# MB_pl_io_v1.net
KiCad netlist of a schematic drawn in Altium Designer
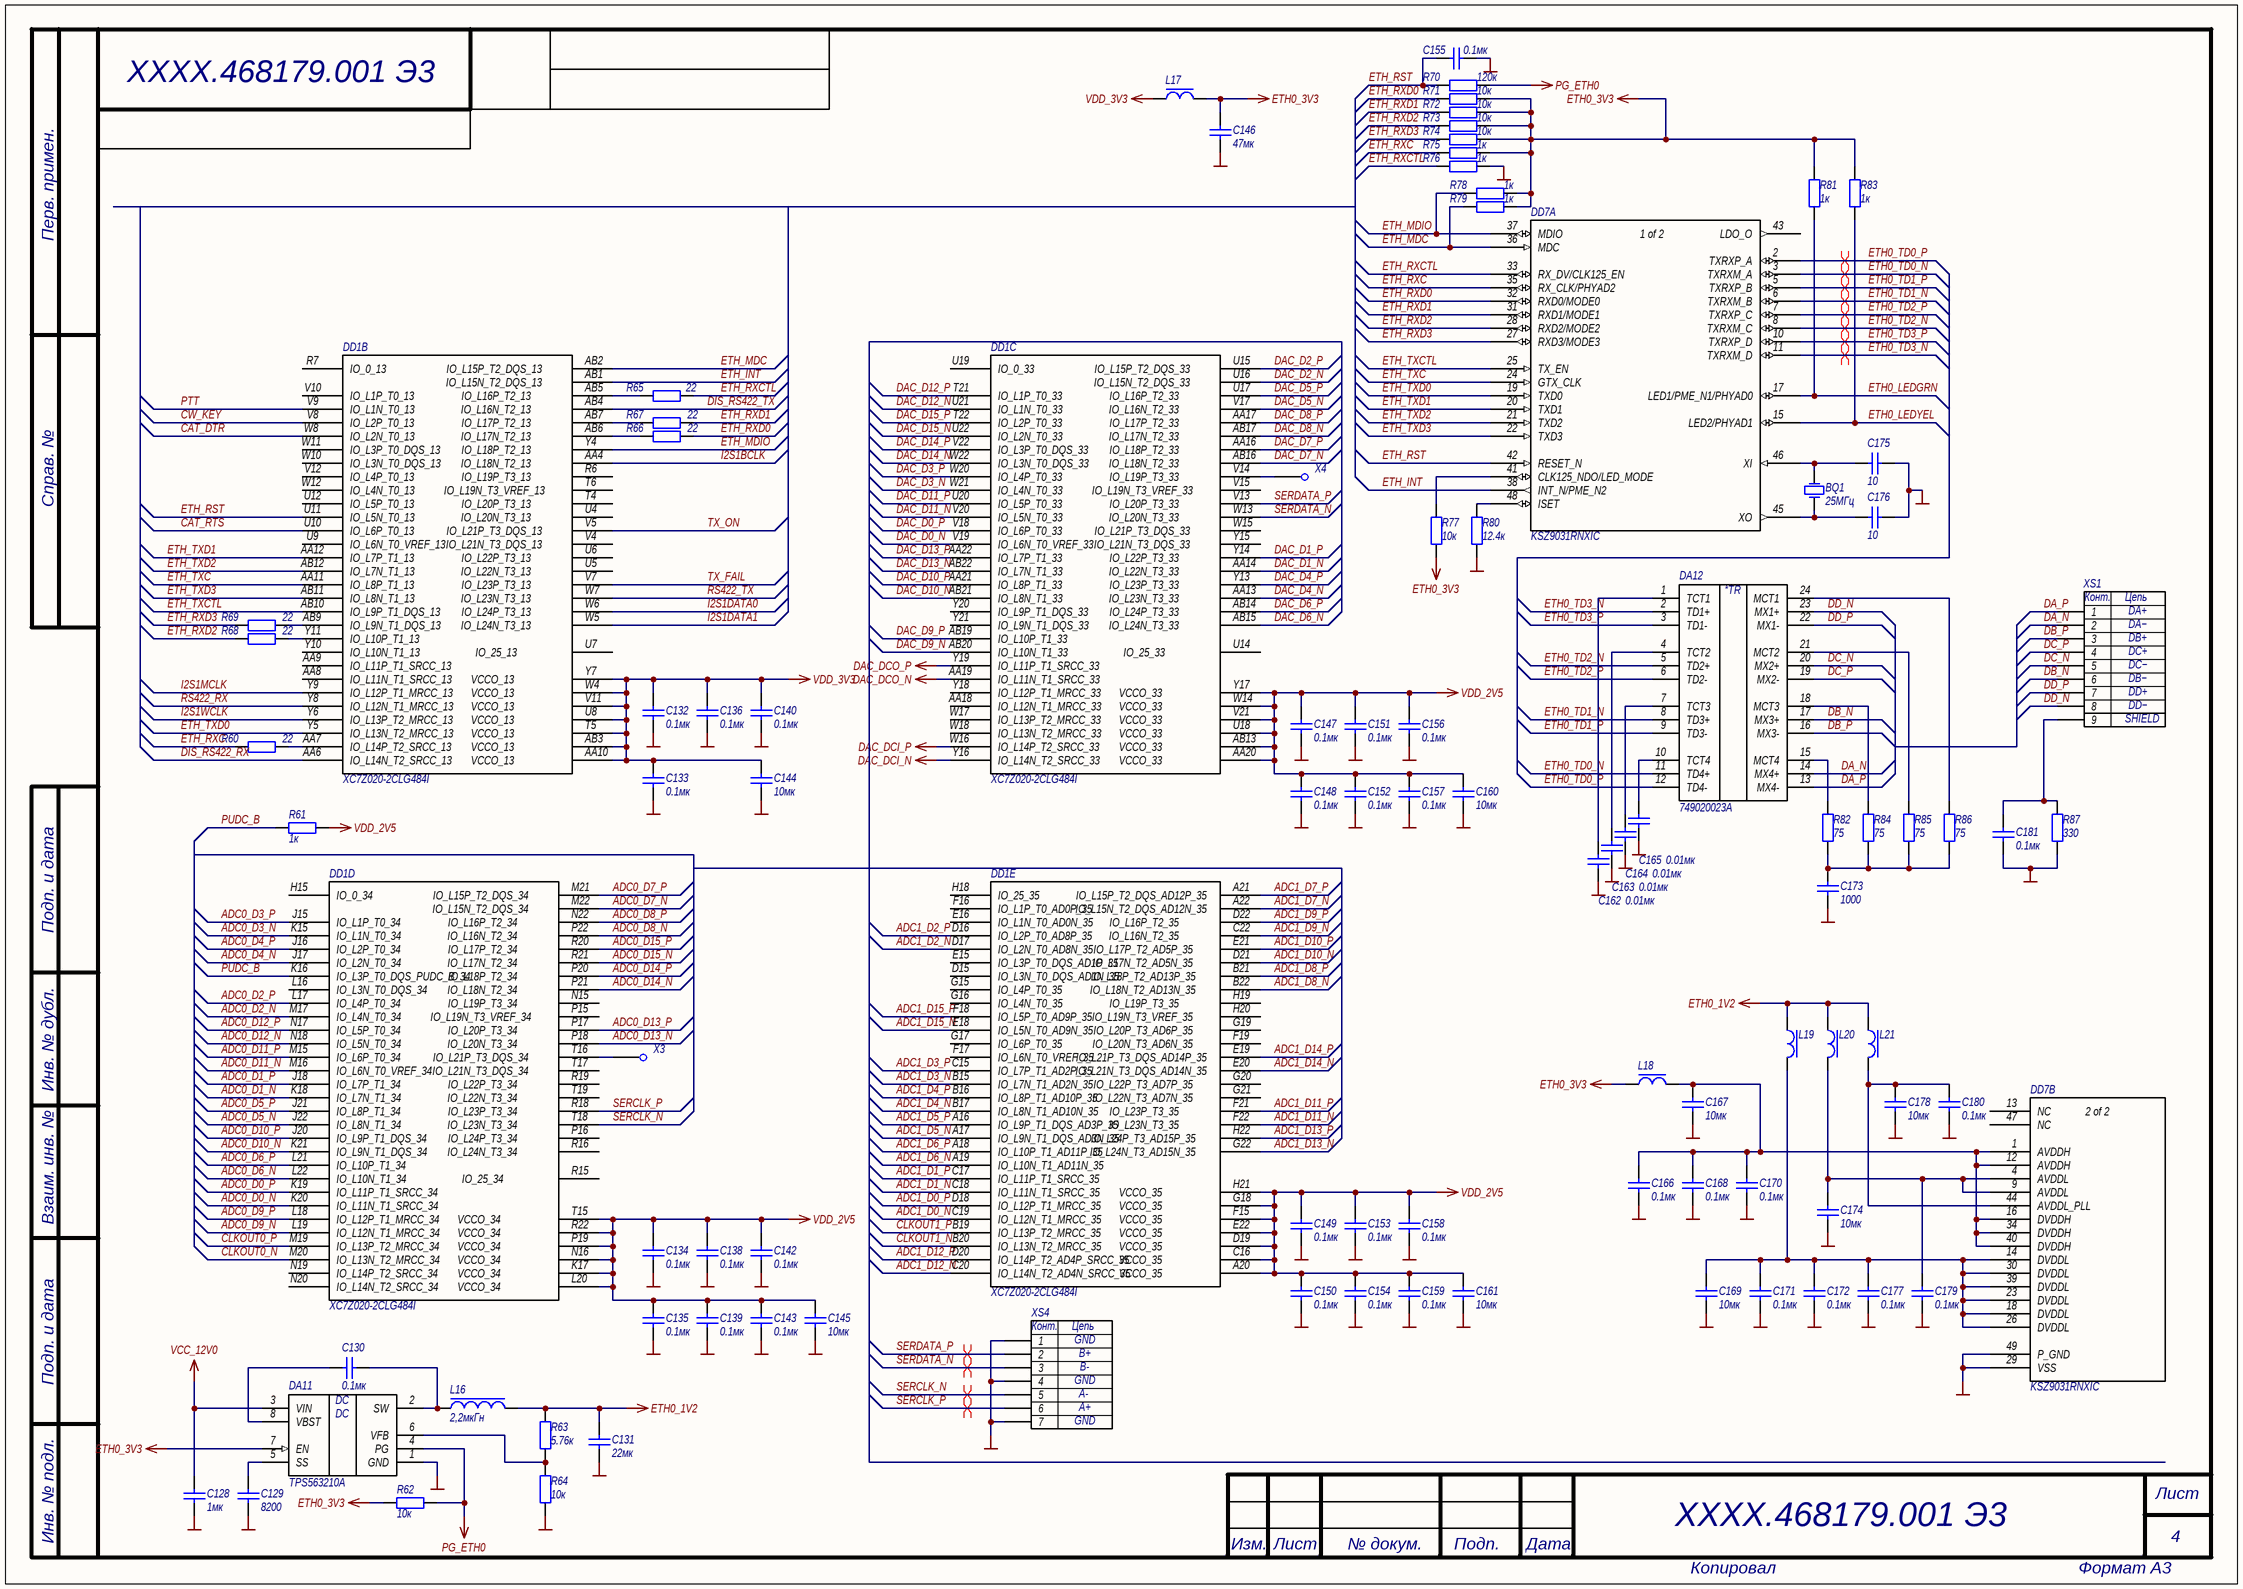
[diagram p0: MB_pl_io_v1.SchDoc]

(export (version "E")
  (design (tool "Eeschema 10.0.6"))
  (components
    (comp (ref "BQ1")
      (value "25МГц")
      (footprint "ABRACOM ABM10")
      (description "Резонатор кварцевый")
      (fields (field (name "TOLERANCE") "±20 ppm") (field (name "MANUFACTURER") "ABRACON"))
      (libsource (lib "nels_other") (part "Кварц ABM10-25.000MHZ-D30"))
    )
    (comp (ref "C128")
      (value "1мк")
      (footprint "CAPC1005X06N")
      (description "Кер. ЧИП-конденсатор")
      (fields (field (name "TOLERANCE") "±10%"))
      (libsource (lib "nels_caps") (part "Кер.ЧИП конд. 0402 1мкФ X5R 10%, 10В"))
    )
    (comp (ref "C129")
      (value "8200")
      (footprint "CAPC1005X06N")
      (description "Кер. ЧИП-конденсатор")
      (fields (field (name "TOLERANCE") "±20%"))
      (libsource (lib "nels_caps") (part "Кер.ЧИП конд. 0402 8200пФ X7R 10%, 50В"))
    )
    (comp (ref "C130")
      (value "0.1мк")
      (footprint "CAPC1005X06N")
      (description "Кер. ЧИП-конденсатор")
      (fields (field (name "TOLERANCE") "±10%"))
      (libsource (lib "nels") (part "Кер.ЧИП конд. 0402 0.1мкФ X7R 10%, 16В"))
    )
    (comp (ref "C131")
      (value "22мк")
      (footprint "CAPC2012X12L")
      (description "Кер. ЧИП-конденсатор")
      (fields (field (name "MANUFACTURER") "TDK") (field (name "TOLERANCE") "±10%"))
      (libsource (lib "nels_caps") (part "Кер.ЧИП конд. 0805 22мкФ X5R 10% 16В"))
    )
    (comp (ref "C132")
      (value "0.1мк")
      (footprint "CAPC1005X06N")
      (description "Кер. ЧИП-конденсатор")
      (fields (field (name "TOLERANCE") "±10%"))
      (libsource (lib "nels") (part "Кер.ЧИП конд. 0402 0.1мкФ X7R 10%, 16В"))
    )
    (comp (ref "C133")
      (value "0.1мк")
      (footprint "CAPC1005X06N")
      (description "Кер. ЧИП-конденсатор")
      (fields (field (name "TOLERANCE") "±10%"))
      (libsource (lib "nels") (part "Кер.ЧИП конд. 0402 0.1мкФ X7R 10%, 16В"))
    )
    (comp (ref "C134")
      (value "0.1мк")
      (footprint "CAPC1005X06N")
      (description "Кер. ЧИП-конденсатор")
      (fields (field (name "TOLERANCE") "±10%"))
      (libsource (lib "nels") (part "Кер.ЧИП конд. 0402 0.1мкФ X7R 10%, 16В"))
    )
    (comp (ref "C135")
      (value "0.1мк")
      (footprint "CAPC1005X06N")
      (description "Кер. ЧИП-конденсатор")
      (fields (field (name "TOLERANCE") "±10%"))
      (libsource (lib "nels") (part "Кер.ЧИП конд. 0402 0.1мкФ X7R 10%, 16В"))
    )
    (comp (ref "C136")
      (value "0.1мк")
      (footprint "CAPC1005X06N")
      (description "Кер. ЧИП-конденсатор")
      (fields (field (name "TOLERANCE") "±10%"))
      (libsource (lib "nels") (part "Кер.ЧИП конд. 0402 0.1мкФ X7R 10%, 16В"))
    )
    (comp (ref "C138")
      (value "0.1мк")
      (footprint "CAPC1005X06N")
      (description "Кер. ЧИП-конденсатор")
      (fields (field (name "TOLERANCE") "±10%"))
      (libsource (lib "nels") (part "Кер.ЧИП конд. 0402 0.1мкФ X7R 10%, 16В"))
    )
    (comp (ref "C139")
      (value "0.1мк")
      (footprint "CAPC1005X06N")
      (description "Кер. ЧИП-конденсатор")
      (fields (field (name "TOLERANCE") "±10%"))
      (libsource (lib "nels") (part "Кер.ЧИП конд. 0402 0.1мкФ X7R 10%, 16В"))
    )
    (comp (ref "C140")
      (value "0.1мк")
      (footprint "CAPC1005X06N")
      (description "Кер. ЧИП-конденсатор")
      (fields (field (name "TOLERANCE") "±10%"))
      (libsource (lib "nels") (part "Кер.ЧИП конд. 0402 0.1мкФ X7R 10%, 16В"))
    )
    (comp (ref "C142")
      (value "0.1мк")
      (footprint "CAPC1005X06N")
      (description "Кер. ЧИП-конденсатор")
      (fields (field (name "TOLERANCE") "±10%"))
      (libsource (lib "nels") (part "Кер.ЧИП конд. 0402 0.1мкФ X7R 10%, 16В"))
    )
    (comp (ref "C143")
      (value "0.1мк")
      (footprint "CAPC1005X06N")
      (description "Кер. ЧИП-конденсатор")
      (fields (field (name "TOLERANCE") "±10%"))
      (libsource (lib "nels") (part "Кер.ЧИП конд. 0402 0.1мкФ X7R 10%, 16В"))
    )
    (comp (ref "C144")
      (value "10мк")
      (footprint "CAPC1608X08L")
      (description "Кер. ЧИП-конденсатор")
      (fields (field (name "MANUFACTURER") "Murata") (field (name "TOLERANCE") "±20%"))
      (libsource (lib "nels_caps") (part "Кер.ЧИП конд. 0603 10мкФ X5R 20% 6.3В"))
    )
    (comp (ref "C145")
      (value "10мк")
      (footprint "CAPC1608X08L")
      (description "Кер. ЧИП-конденсатор")
      (fields (field (name "MANUFACTURER") "Murata") (field (name "TOLERANCE") "±20%"))
      (libsource (lib "nels_caps") (part "Кер.ЧИП конд. 0603 10мкФ X5R 20% 6.3В"))
    )
    (comp (ref "C146")
      (value "47мк")
      (footprint "CAPC2012X12L")
      (description "Кер. ЧИП-конденсатор")
      (fields (field (name "MANUFACTURER") "Murata") (field (name "TOLERANCE") "±20%"))
      (libsource (lib "nels_caps") (part "Кер.ЧИП конд. 0805 47мкФ X5R 20% 10В"))
    )
    (comp (ref "C147")
      (value "0.1мк")
      (footprint "CAPC1005X06N")
      (description "Кер. ЧИП-конденсатор")
      (fields (field (name "TOLERANCE") "±10%"))
      (libsource (lib "nels") (part "Кер.ЧИП конд. 0402 0.1мкФ X7R 10%, 16В"))
    )
    (comp (ref "C148")
      (value "0.1мк")
      (footprint "CAPC1005X06N")
      (description "Кер. ЧИП-конденсатор")
      (fields (field (name "TOLERANCE") "±10%"))
      (libsource (lib "nels") (part "Кер.ЧИП конд. 0402 0.1мкФ X7R 10%, 16В"))
    )
    (comp (ref "C149")
      (value "0.1мк")
      (footprint "CAPC1005X06N")
      (description "Кер. ЧИП-конденсатор")
      (fields (field (name "TOLERANCE") "±10%"))
      (libsource (lib "nels") (part "Кер.ЧИП конд. 0402 0.1мкФ X7R 10%, 16В"))
    )
    (comp (ref "C150")
      (value "0.1мк")
      (footprint "CAPC1005X06N")
      (description "Кер. ЧИП-конденсатор")
      (fields (field (name "TOLERANCE") "±10%"))
      (libsource (lib "nels") (part "Кер.ЧИП конд. 0402 0.1мкФ X7R 10%, 16В"))
    )
    (comp (ref "C151")
      (value "0.1мк")
      (footprint "CAPC1005X06N")
      (description "Кер. ЧИП-конденсатор")
      (fields (field (name "TOLERANCE") "±10%"))
      (libsource (lib "nels") (part "Кер.ЧИП конд. 0402 0.1мкФ X7R 10%, 16В"))
    )
    (comp (ref "C152")
      (value "0.1мк")
      (footprint "CAPC1005X06N")
      (description "Кер. ЧИП-конденсатор")
      (fields (field (name "TOLERANCE") "±10%"))
      (libsource (lib "nels") (part "Кер.ЧИП конд. 0402 0.1мкФ X7R 10%, 16В"))
    )
    (comp (ref "C153")
      (value "0.1мк")
      (footprint "CAPC1005X06N")
      (description "Кер. ЧИП-конденсатор")
      (fields (field (name "TOLERANCE") "±10%"))
      (libsource (lib "nels") (part "Кер.ЧИП конд. 0402 0.1мкФ X7R 10%, 16В"))
    )
    (comp (ref "C154")
      (value "0.1мк")
      (footprint "CAPC1005X06N")
      (description "Кер. ЧИП-конденсатор")
      (fields (field (name "TOLERANCE") "±10%"))
      (libsource (lib "nels") (part "Кер.ЧИП конд. 0402 0.1мкФ X7R 10%, 16В"))
    )
    (comp (ref "C155")
      (value "0.1мк")
      (footprint "CAPC1005X06N")
      (description "Кер. ЧИП-конденсатор")
      (fields (field (name "TOLERANCE") "±10%"))
      (libsource (lib "nels") (part "Кер.ЧИП конд. 0402 0.1мкФ X7R 10%, 16В"))
    )
    (comp (ref "C156")
      (value "0.1мк")
      (footprint "CAPC1005X06N")
      (description "Кер. ЧИП-конденсатор")
      (fields (field (name "TOLERANCE") "±10%"))
      (libsource (lib "nels") (part "Кер.ЧИП конд. 0402 0.1мкФ X7R 10%, 16В"))
    )
    (comp (ref "C157")
      (value "0.1мк")
      (footprint "CAPC1005X06N")
      (description "Кер. ЧИП-конденсатор")
      (fields (field (name "TOLERANCE") "±10%"))
      (libsource (lib "nels") (part "Кер.ЧИП конд. 0402 0.1мкФ X7R 10%, 16В"))
    )
    (comp (ref "C158")
      (value "0.1мк")
      (footprint "CAPC1005X06N")
      (description "Кер. ЧИП-конденсатор")
      (fields (field (name "TOLERANCE") "±10%"))
      (libsource (lib "nels") (part "Кер.ЧИП конд. 0402 0.1мкФ X7R 10%, 16В"))
    )
    (comp (ref "C159")
      (value "0.1мк")
      (footprint "CAPC1005X06N")
      (description "Кер. ЧИП-конденсатор")
      (fields (field (name "TOLERANCE") "±10%"))
      (libsource (lib "nels") (part "Кер.ЧИП конд. 0402 0.1мкФ X7R 10%, 16В"))
    )
    (comp (ref "C160")
      (value "10мк")
      (footprint "CAPC1608X08L")
      (description "Кер. ЧИП-конденсатор")
      (fields (field (name "MANUFACTURER") "Murata") (field (name "TOLERANCE") "±20%"))
      (libsource (lib "nels_caps") (part "Кер.ЧИП конд. 0603 10мкФ X5R 20% 6.3В"))
    )
    (comp (ref "C161")
      (value "10мк")
      (footprint "CAPC1608X08L")
      (description "Кер. ЧИП-конденсатор")
      (fields (field (name "MANUFACTURER") "Murata") (field (name "TOLERANCE") "±20%"))
      (libsource (lib "nels_caps") (part "Кер.ЧИП конд. 0603 10мкФ X5R 20% 6.3В"))
    )
    (comp (ref "C162")
      (value "0.01мк")
      (footprint "CAPC1005X06N")
      (description "Кер. ЧИП-конденсатор")
      (fields (field (name "TOLERANCE") "±20%"))
      (libsource (lib "nels_caps") (part "Кер.ЧИП конд. 0402 0.01мкФ X7R 10%, 50В"))
    )
    (comp (ref "C163")
      (value "0.01мк")
      (footprint "CAPC1005X06N")
      (description "Кер. ЧИП-конденсатор")
      (fields (field (name "TOLERANCE") "±20%"))
      (libsource (lib "nels_caps") (part "Кер.ЧИП конд. 0402 0.01мкФ X7R 10%, 50В"))
    )
    (comp (ref "C164")
      (value "0.01мк")
      (footprint "CAPC1005X06N")
      (description "Кер. ЧИП-конденсатор")
      (fields (field (name "TOLERANCE") "±20%"))
      (libsource (lib "nels_caps") (part "Кер.ЧИП конд. 0402 0.01мкФ X7R 10%, 50В"))
    )
    (comp (ref "C165")
      (value "0.01мк")
      (footprint "CAPC1005X06N")
      (description "Кер. ЧИП-конденсатор")
      (fields (field (name "TOLERANCE") "±20%"))
      (libsource (lib "nels_caps") (part "Кер.ЧИП конд. 0402 0.01мкФ X7R 10%, 50В"))
    )
    (comp (ref "C166")
      (value "0.1мк")
      (footprint "CAPC1005X06N")
      (description "Кер. ЧИП-конденсатор")
      (fields (field (name "TOLERANCE") "±10%"))
      (libsource (lib "nels_caps") (part "Кер.ЧИП конд. 0402 0.1мкФ X7R 10%, 16В"))
    )
    (comp (ref "C167")
      (value "10мк")
      (footprint "CAPC1608X08L")
      (description "Кер. ЧИП-конденсатор")
      (fields (field (name "MANUFACTURER") "Murata") (field (name "TOLERANCE") "±20%"))
      (libsource (lib "nels_caps") (part "Кер.ЧИП конд. 0603 10мкФ X5R 20% 6.3В"))
    )
    (comp (ref "C168")
      (value "0.1мк")
      (footprint "CAPC1005X06N")
      (description "Кер. ЧИП-конденсатор")
      (fields (field (name "TOLERANCE") "±10%"))
      (libsource (lib "nels_caps") (part "Кер.ЧИП конд. 0402 0.1мкФ X7R 10%, 16В"))
    )
    (comp (ref "C169")
      (value "10мк")
      (footprint "CAPC1608X08L")
      (description "Кер. ЧИП-конденсатор")
      (fields (field (name "MANUFACTURER") "Murata") (field (name "TOLERANCE") "±20%"))
      (libsource (lib "nels_caps") (part "Кер.ЧИП конд. 0603 10мкФ X5R 20% 6.3В"))
    )
    (comp (ref "C170")
      (value "0.1мк")
      (footprint "CAPC1005X06N")
      (description "Кер. ЧИП-конденсатор")
      (fields (field (name "TOLERANCE") "±10%"))
      (libsource (lib "nels_caps") (part "Кер.ЧИП конд. 0402 0.1мкФ X7R 10%, 16В"))
    )
    (comp (ref "C171")
      (value "0.1мк")
      (footprint "CAPC1005X06N")
      (description "Кер. ЧИП-конденсатор")
      (fields (field (name "TOLERANCE") "±10%"))
      (libsource (lib "nels_caps") (part "Кер.ЧИП конд. 0402 0.1мкФ X7R 10%, 16В"))
    )
    (comp (ref "C172")
      (value "0.1мк")
      (footprint "CAPC1005X06N")
      (description "Кер. ЧИП-конденсатор")
      (fields (field (name "TOLERANCE") "±10%"))
      (libsource (lib "nels_caps") (part "Кер.ЧИП конд. 0402 0.1мкФ X7R 10%, 16В"))
    )
    (comp (ref "C173")
      (value "1000")
      (footprint "CAPC1005X06N")
      (description "Кер. ЧИП-конденсатор")
      (fields (field (name "TOLERANCE") "±5%"))
      (libsource (lib "nels_caps") (part "Кер.ЧИП конд. 0402 1000пФ NP0 5%, 50В"))
    )
    (comp (ref "C174")
      (value "10мк")
      (footprint "CAPC1608X08L")
      (description "Кер. ЧИП-конденсатор")
      (fields (field (name "MANUFACTURER") "Murata") (field (name "TOLERANCE") "±20%"))
      (libsource (lib "nels_caps") (part "Кер.ЧИП конд. 0603 10мкФ X5R 20% 6.3В"))
    )
    (comp (ref "C175")
      (value "10")
      (footprint "CAPC1005X06N")
      (description "Кер. ЧИП-конденсатор")
      (fields (field (name "TOLERANCE") "±5%"))
      (libsource (lib "nels_caps") (part "Кер.ЧИП конд. 0402 10пФ NPO 5%, 50В"))
    )
    (comp (ref "C176")
      (value "10")
      (footprint "CAPC1005X06N")
      (description "Кер. ЧИП-конденсатор")
      (fields (field (name "TOLERANCE") "±5%"))
      (libsource (lib "nels_caps") (part "Кер.ЧИП конд. 0402 10пФ NPO 5%, 50В"))
    )
    (comp (ref "C177")
      (value "0.1мк")
      (footprint "CAPC1005X06N")
      (description "Кер. ЧИП-конденсатор")
      (fields (field (name "TOLERANCE") "±10%"))
      (libsource (lib "nels_caps") (part "Кер.ЧИП конд. 0402 0.1мкФ X7R 10%, 16В"))
    )
    (comp (ref "C178")
      (value "10мк")
      (footprint "CAPC1608X08L")
      (description "Кер. ЧИП-конденсатор")
      (fields (field (name "MANUFACTURER") "Murata") (field (name "TOLERANCE") "±20%"))
      (libsource (lib "nels_caps") (part "Кер.ЧИП конд. 0603 10мкФ X5R 20% 6.3В"))
    )
    (comp (ref "C179")
      (value "0.1мк")
      (footprint "CAPC1005X06N")
      (description "Кер. ЧИП-конденсатор")
      (fields (field (name "TOLERANCE") "±10%"))
      (libsource (lib "nels_caps") (part "Кер.ЧИП конд. 0402 0.1мкФ X7R 10%, 16В"))
    )
    (comp (ref "C180")
      (value "0.1мк")
      (footprint "CAPC1005X06N")
      (description "Кер. ЧИП-конденсатор")
      (fields (field (name "TOLERANCE") "±10%"))
      (libsource (lib "nels_caps") (part "Кер.ЧИП конд. 0402 0.1мкФ X7R 10%, 16В"))
    )
    (comp (ref "C181")
      (value "0.1мк")
      (footprint "CAPC1608X08L")
      (description "Кер. ЧИП-конденсатор")
      (fields (field (name "TOLERANCE") "±10%") (field (name "MANUFACTURER") "Murata"))
      (libsource (lib "nels_caps") (part "Кер.ЧИП конд. 0603 0.1мкФ X7R 10% 50В"))
    )
    (comp (ref "DA11")
      (value "TPS563210A")
      (footprint "TSOP65P280X110-8N")
      (description "TPS56x210A, 4.5-V to 17-V Input, 2-A, 3-A Synchrono")
      (fields (field (name "MANUFACTURER") "TI"))
      (libsource (lib "MB") (part "Микросхема TPS563210A"))
    )
    (comp (ref "DA12")
      (value "749020023A")
      (footprint "749020023A")
      (description "1000BASE-T Magnetics Module")
      (fields (field (name "MANUFACTURER") "Wurth Elektronik"))
      (libsource (lib "nels_other") (part "Сборка трансформаторов 749020023A"))
    )
    (comp (ref "DD1")
      (value "XC7Z020-2CLG484I")
      (footprint "BGA484C80P22X22_1900X1900X160")
      (description "Zynq®-7000 SoC Family")
      (fields (field (name "MANUFACTURER") "XILINX"))
      (libsource (lib "MB") (part "Микросхема XC7Z020-2CLG484I"))
    )
    (comp (ref "DD7")
      (value "KSZ9031RNXIC")
      (footprint "QFN50P700X700-48V6M")
      (description "Gigabit Ethernet Transceiver with Power Saving Features")
      (fields (field (name "COPYRIGHT") "Copyright (C) 2018 Accelerated Designs. All rights reserved"))
      (libsource (lib "nels_chip") (part "Микросхема KSZ9031RNXIC"))
    )
    (comp (ref "L16")
      (value "2,2мкГн")
      (footprint "CSAB0420")
      (description "Molding Power Choke")
      (fields
        (field (name "MANUFACTURER") "Vishay")
        (field (name "MANUFACTURERPARTNUMBER") "IHLP1616ABER1R0M11")
      )
      (libsource (lib "nels_ind") (part "ЧИП индуктивность CSAB0420-2R2M"))
    )
    (comp (ref "L17")
      (value "BLM18PG121SN1D")
      (footprint "INDC1608X08L")
      (description "SMD EMI Suppression Filter EMIFIL")
      (fields (field (name "MANUFACTURER") "Murata"))
      (libsource (lib "nels_ind") (part "ЧИП дроссель 0603 BLM18PG121SN1D"))
    )
    (comp (ref "L18")
      (value "BLM18PG121SN1D")
      (footprint "INDC1608X08L")
      (description "SMD EMI Suppression Filter EMIFIL")
      (fields (field (name "MANUFACTURER") "Murata"))
      (libsource (lib "nels_ind") (part "ЧИП дроссель 0603 BLM18PG121SN1D"))
    )
    (comp (ref "L19")
      (value "BLM18PG121SN1D")
      (footprint "INDC1608X08L")
      (description "SMD EMI Suppression Filter EMIFIL")
      (fields (field (name "MANUFACTURER") "Murata"))
      (libsource (lib "nels_ind") (part "ЧИП дроссель 0603 BLM18PG121SN1D"))
    )
    (comp (ref "L20")
      (value "BLM18PG121SN1D")
      (footprint "INDC1608X08L")
      (description "SMD EMI Suppression Filter EMIFIL")
      (fields (field (name "MANUFACTURER") "Murata"))
      (libsource (lib "nels_ind") (part "ЧИП дроссель 0603 BLM18PG121SN1D"))
    )
    (comp (ref "L21")
      (value "BLM18PG121SN1D")
      (footprint "INDC1608X08L")
      (description "SMD EMI Suppression Filter EMIFIL")
      (fields (field (name "MANUFACTURER") "Murata"))
      (libsource (lib "nels_ind") (part "ЧИП дроссель 0603 BLM18PG121SN1D"))
    )
    (comp (ref "R60")
      (value "22")
      (footprint "RESC1005X06N")
      (description "ЧИП-резистор")
      (fields (field (name "TOLERANCE") "±5%"))
      (libsource (lib "nels_res") (part "Чип резистор 0402 22 Ом, 5%"))
    )
    (comp (ref "R61")
      (value "1к")
      (footprint "RESC1005X06N")
      (description "ЧИП-резистор")
      (fields (field (name "TOLERANCE") "±5%"))
      (libsource (lib "nels_res") (part "Чип резистор 0402 1 кОм, 5%"))
    )
    (comp (ref "R62")
      (value "10к")
      (footprint "RESC1005X06N")
      (description "ЧИП-резистор")
      (fields (field (name "TOLERANCE") "±5%"))
      (libsource (lib "nels_res") (part "Чип резистор 0402 10 кОм, 1%"))
    )
    (comp (ref "R63")
      (value "5.76к")
      (footprint "RESC1005X06N")
      (description "ЧИП-резистор")
      (fields (field (name "TOLERANCE") "±1%"))
      (libsource (lib "nels_res") (part "Чип резистор 0402 5,76 кОм, 1%"))
    )
    (comp (ref "R64")
      (value "10к")
      (footprint "RESC1005X06N")
      (description "ЧИП-резистор")
      (fields (field (name "TOLERANCE") "±5%"))
      (libsource (lib "") (part "Чип резистор 0402 10 кОм, 5%_1"))
    )
    (comp (ref "R65")
      (value "22")
      (footprint "RESC1005X06N")
      (description "ЧИП-резистор")
      (fields (field (name "TOLERANCE") "±5%"))
      (libsource (lib "") (part "Чип резистор 0402 22 Ом, 5%_1"))
    )
    (comp (ref "R66")
      (value "22")
      (footprint "RESC1005X06N")
      (description "ЧИП-резистор")
      (fields (field (name "TOLERANCE") "±5%"))
      (libsource (lib "nels_res") (part "Чип резистор 0402 22 Ом, 5%"))
    )
    (comp (ref "R67")
      (value "22")
      (footprint "RESC1005X06N")
      (description "ЧИП-резистор")
      (fields (field (name "TOLERANCE") "±5%"))
      (libsource (lib "nels_res") (part "Чип резистор 0402 22 Ом, 5%"))
    )
    (comp (ref "R68")
      (value "22")
      (footprint "RESC1005X06N")
      (description "ЧИП-резистор")
      (fields (field (name "TOLERANCE") "±5%"))
      (libsource (lib "nels_res") (part "Чип резистор 0402 22 Ом, 5%"))
    )
    (comp (ref "R69")
      (value "22")
      (footprint "RESC1005X06N")
      (description "ЧИП-резистор")
      (fields (field (name "TOLERANCE") "±5%"))
      (libsource (lib "nels_res") (part "Чип резистор 0402 22 Ом, 5%"))
    )
    (comp (ref "R70")
      (value "120к")
      (footprint "RESC1005X06N")
      (description "ЧИП-резистор")
      (fields (field (name "TOLERANCE") "±5%"))
      (libsource (lib "nels_res") (part "Чип резистор 0402 120 кОм, 5%"))
    )
    (comp (ref "R71")
      (value "10к")
      (footprint "RESC1005X06N")
      (description "ЧИП-резистор")
      (fields (field (name "TOLERANCE") "±5%"))
      (libsource (lib "nels_res") (part "Чип резистор 0402 10 кОм, 5%"))
    )
    (comp (ref "R72")
      (value "10к")
      (footprint "RESC1005X06N")
      (description "ЧИП-резистор")
      (fields (field (name "TOLERANCE") "±5%"))
      (libsource (lib "nels_res") (part "Чип резистор 0402 10 кОм, 5%"))
    )
    (comp (ref "R73")
      (value "10к")
      (footprint "RESC1005X06N")
      (description "ЧИП-резистор")
      (fields (field (name "TOLERANCE") "±5%"))
      (libsource (lib "nels_res") (part "Чип резистор 0402 10 кОм, 5%"))
    )
    (comp (ref "R74")
      (value "10к")
      (footprint "RESC1005X06N")
      (description "ЧИП-резистор")
      (fields (field (name "TOLERANCE") "±5%"))
      (libsource (lib "nels_res") (part "Чип резистор 0402 10 кОм, 5%"))
    )
    (comp (ref "R75")
      (value "1к")
      (footprint "RESC1005X06N")
      (description "ЧИП-резистор")
      (fields (field (name "TOLERANCE") "±5%"))
      (libsource (lib "nels_res") (part "Чип резистор 0402 1 кОм, 5%"))
    )
    (comp (ref "R76")
      (value "1к")
      (footprint "RESC1005X06N")
      (description "ЧИП-резистор")
      (fields (field (name "TOLERANCE") "±5%"))
      (libsource (lib "nels_res") (part "Чип резистор 0402 1 кОм, 5%"))
    )
    (comp (ref "R77")
      (value "10к")
      (footprint "RESC1005X06N")
      (description "ЧИП-резистор")
      (fields (field (name "TOLERANCE") "±5%"))
      (libsource (lib "") (part "Чип резистор 0402 10 кОм, 5%_1"))
    )
    (comp (ref "R78")
      (value "1к")
      (footprint "RESC1005X06N")
      (description "ЧИП-резистор")
      (fields (field (name "TOLERANCE") "±5%"))
      (libsource (lib "nels_res") (part "Чип резистор 0402 1 кОм, 5%"))
    )
    (comp (ref "R79")
      (value "1к")
      (footprint "RESC1005X06N")
      (description "ЧИП-резистор")
      (fields (field (name "TOLERANCE") "±5%"))
      (libsource (lib "nels_res") (part "Чип резистор 0402 1 кОм, 5%"))
    )
    (comp (ref "R80")
      (value "12.4к")
      (footprint "RESC1005X06N")
      (description "ЧИП-резистор")
      (fields (field (name "TOLERANCE") "±1%"))
      (libsource (lib "nels_res") (part "Чип резистор 0402 12.4 кОм, 1%"))
    )
    (comp (ref "R81")
      (value "1к")
      (footprint "RESC1005X06N")
      (description "ЧИП-резистор")
      (fields (field (name "TOLERANCE") "±5%"))
      (libsource (lib "") (part "Чип резистор 0402 1 кОм, 5%_1"))
    )
    (comp (ref "R82")
      (value "75")
      (footprint "RESC1005X06N")
      (description "ЧИП-резистор")
      (fields (field (name "TOLERANCE") "±5%"))
      (libsource (lib "nels_res") (part "Чип резистор 0402 75 Ом, 5%"))
    )
    (comp (ref "R83")
      (value "1к")
      (footprint "RESC1005X06N")
      (description "ЧИП-резистор")
      (fields (field (name "TOLERANCE") "±5%"))
      (libsource (lib "") (part "Чип резистор 0402 1 кОм, 5%_1"))
    )
    (comp (ref "R84")
      (value "75")
      (footprint "RESC1005X06N")
      (description "ЧИП-резистор")
      (fields (field (name "TOLERANCE") "±5%"))
      (libsource (lib "nels_res") (part "Чип резистор 0402 75 Ом, 5%"))
    )
    (comp (ref "R85")
      (value "75")
      (footprint "RESC1005X06N")
      (description "ЧИП-резистор")
      (fields (field (name "TOLERANCE") "±5%"))
      (libsource (lib "nels_res") (part "Чип резистор 0402 75 Ом, 5%"))
    )
    (comp (ref "R86")
      (value "75")
      (footprint "RESC1005X06N")
      (description "ЧИП-резистор")
      (fields (field (name "TOLERANCE") "±5%"))
      (libsource (lib "nels_res") (part "Чип резистор 0402 75 Ом, 5%"))
    )
    (comp (ref "R87")
      (value "330")
      (footprint "RESC1005X06N")
      (description "ЧИП-резистор")
      (fields (field (name "TOLERANCE") "±5%"))
      (libsource (lib "nels_res") (part "Чип резистор 0402 330 Ом, 5%"))
    )
    (comp (ref "X3")
      (value "Конструктивный элемент")
      (footprint "PIN2_PROBE")
      (description "Соединитель")
      (libsource (lib "nels_conn") (part "Соединение под пайку"))
    )
    (comp (ref "X4")
      (value "Конструктивный элемент")
      (footprint "PIN2_PROBE")
      (description "Соединитель")
      (libsource (lib "nels_conn") (part "Соединение под пайку"))
    )
    (comp (ref "XS1")
      (value "TJ16S-8P8C")
      (footprint "KLS12-107L")
      (description "Modular Jack RJ45")
      (fields (field (name "MANUFACTURER") "KLS"))
      (libsource (lib "nels_conn") (part "Соединитель KLS12-107L-2-8P8C-0"))
    )
    (comp (ref "XS4")
      (value "KLS1-SATA001")
      (footprint "KLS1-SATA001")
      (description "SATA Type A 7P Male Connector,SMD")
      (fields (field (name "MANUFACTURER") "KLS"))
      (libsource (lib "nels_conn") (part "Соединитель KLS1-SATA001"))
    )
  )
  (nets
    (net (code "1") (name "/ADC0_D0_N") (class "Default")
      (node (ref "DD1") (pin "K20") (pinfunction "IO_L11N_T1_SRCC_34_K20") (pintype "passive"))
    )
    (net (code "2") (name "/ADC0_D0_P") (class "Default")
      (node (ref "DD1") (pin "K19") (pinfunction "IO_L11P_T1_SRCC_34_K19") (pintype "passive"))
    )
    (net (code "3") (name "/ADC0_D1_N") (class "Default")
      (node (ref "DD1") (pin "K18") (pinfunction "IO_L7N_T1_34_K18") (pintype "passive"))
    )
    (net (code "4") (name "/ADC0_D1_P") (class "Default")
      (node (ref "DD1") (pin "J18") (pinfunction "IO_L7P_T1_34_J18") (pintype "passive"))
    )
    (net (code "5") (name "/ADC0_D2_N") (class "Default")
      (node (ref "DD1") (pin "M17") (pinfunction "IO_L4N_T0_34_M17") (pintype "passive"))
    )
    (net (code "6") (name "/ADC0_D2_P") (class "Default")
      (node (ref "DD1") (pin "L17") (pinfunction "IO_L4P_T0_34_L17") (pintype "passive"))
    )
    (net (code "7") (name "/ADC0_D3_N") (class "Default")
      (node (ref "DD1") (pin "K15") (pinfunction "IO_L1N_T0_34_K15") (pintype "passive"))
    )
    (net (code "8") (name "/ADC0_D3_P") (class "Default")
      (node (ref "DD1") (pin "J15") (pinfunction "IO_L1P_T0_34_J15") (pintype "passive"))
    )
    (net (code "9") (name "/ADC0_D4_N") (class "Default")
      (node (ref "DD1") (pin "J17") (pinfunction "IO_L2N_T0_34_J17") (pintype "passive"))
    )
    (net (code "10") (name "/ADC0_D4_P") (class "Default")
      (node (ref "DD1") (pin "J16") (pinfunction "IO_L2P_T0_34_J16") (pintype "passive"))
    )
    (net (code "11") (name "/ADC0_D5_N") (class "Default")
      (node (ref "DD1") (pin "J22") (pinfunction "IO_L8N_T1_34_J22") (pintype "passive"))
    )
    (net (code "12") (name "/ADC0_D5_P") (class "Default")
      (node (ref "DD1") (pin "J21") (pinfunction "IO_L8P_T1_34_J21") (pintype "passive"))
    )
    (net (code "13") (name "/ADC0_D6_N") (class "Default")
      (node (ref "DD1") (pin "L22") (pinfunction "IO_L10N_T1_34_L22") (pintype "passive"))
    )
    (net (code "14") (name "/ADC0_D6_P") (class "Default")
      (node (ref "DD1") (pin "L21") (pinfunction "IO_L10P_T1_34_L21") (pintype "passive"))
    )
    (net (code "15") (name "/ADC0_D7_N") (class "Default")
      (node (ref "DD1") (pin "M22") (pinfunction "IO_L15N_T2_DQS_34_M22") (pintype "passive"))
    )
    (net (code "16") (name "/ADC0_D7_P") (class "Default")
      (node (ref "DD1") (pin "M21") (pinfunction "IO_L15P_T2_DQS_34_M21") (pintype "passive"))
    )
    (net (code "17") (name "/ADC0_D8_N") (class "Default")
      (node (ref "DD1") (pin "P22") (pinfunction "IO_L16N_T2_34_P22") (pintype "passive"))
    )
    (net (code "18") (name "/ADC0_D8_P") (class "Default")
      (node (ref "DD1") (pin "N22") (pinfunction "IO_L16P_T2_34_N22") (pintype "passive"))
    )
    (net (code "19") (name "/ADC0_D9_N") (class "Default")
      (node (ref "DD1") (pin "L19") (pinfunction "IO_L12N_T1_MRCC_34_L19") (pintype "passive"))
    )
    (net (code "20") (name "/ADC0_D9_P") (class "Default")
      (node (ref "DD1") (pin "L18") (pinfunction "IO_L12P_T1_MRCC_34_L18") (pintype "passive"))
    )
    (net (code "21") (name "/ADC0_D10_N") (class "Default")
      (node (ref "DD1") (pin "K21") (pinfunction "IO_L9N_T1_DQS_34_K21") (pintype "passive"))
    )
    (net (code "22") (name "/ADC0_D10_P") (class "Default")
      (node (ref "DD1") (pin "J20") (pinfunction "IO_L9P_T1_DQS_34_J20") (pintype "passive"))
    )
    (net (code "23") (name "/ADC0_D11_N") (class "Default")
      (node (ref "DD1") (pin "M16") (pinfunction "IO_L6N_T0_VREF_34_M16") (pintype "passive"))
    )
    (net (code "24") (name "/ADC0_D11_P") (class "Default")
      (node (ref "DD1") (pin "M15") (pinfunction "IO_L6P_T0_34_M15") (pintype "passive"))
    )
    (net (code "25") (name "/ADC0_D12_N") (class "Default")
      (node (ref "DD1") (pin "N18") (pinfunction "IO_L5N_T0_34_N18") (pintype "passive"))
    )
    (net (code "26") (name "/ADC0_D12_P") (class "Default")
      (node (ref "DD1") (pin "N17") (pinfunction "IO_L5P_T0_34_N17") (pintype "passive"))
    )
    (net (code "27") (name "/ADC0_D13_N") (class "Default")
      (node (ref "DD1") (pin "P18") (pinfunction "IO_L20N_T3_34_P18") (pintype "passive"))
    )
    (net (code "28") (name "/ADC0_D13_P") (class "Default")
      (node (ref "DD1") (pin "P17") (pinfunction "IO_L20P_T3_34_P17") (pintype "passive"))
    )
    (net (code "29") (name "/ADC0_D14_N") (class "Default")
      (node (ref "DD1") (pin "P21") (pinfunction "IO_L18N_T2_34_P21") (pintype "passive"))
    )
    (net (code "30") (name "/ADC0_D14_P") (class "Default")
      (node (ref "DD1") (pin "P20") (pinfunction "IO_L18P_T2_34_P20") (pintype "passive"))
    )
    (net (code "31") (name "/ADC0_D15_N") (class "Default")
      (node (ref "DD1") (pin "R21") (pinfunction "IO_L17N_T2_34_R21") (pintype "passive"))
    )
    (net (code "32") (name "/ADC0_D15_P") (class "Default")
      (node (ref "DD1") (pin "R20") (pinfunction "IO_L17P_T2_34_R20") (pintype "passive"))
    )
    (net (code "33") (name "/ADC1_D0_N") (class "Default")
      (node (ref "DD1") (pin "C19") (pinfunction "IO_L12N_T1_MRCC_35_C19") (pintype "passive"))
    )
    (net (code "34") (name "/ADC1_D0_P") (class "Default")
      (node (ref "DD1") (pin "D18") (pinfunction "IO_L12P_T1_MRCC_35_D18") (pintype "passive"))
    )
    (net (code "35") (name "/ADC1_D1_N") (class "Default")
      (node (ref "DD1") (pin "C18") (pinfunction "IO_L11N_T1_SRCC_35_C18") (pintype "passive"))
    )
    (net (code "36") (name "/ADC1_D1_P") (class "Default")
      (node (ref "DD1") (pin "C17") (pinfunction "IO_L11P_T1_SRCC_35_C17") (pintype "passive"))
    )
    (net (code "37") (name "/ADC1_D2_N") (class "Default")
      (node (ref "DD1") (pin "D17") (pinfunction "IO_L2N_T0_AD8N_35_D17") (pintype "passive"))
    )
    (net (code "38") (name "/ADC1_D2_P") (class "Default")
      (node (ref "DD1") (pin "D16") (pinfunction "IO_L2P_T0_AD8P_35_D16") (pintype "passive"))
    )
    (net (code "39") (name "/ADC1_D3_N") (class "Default")
      (node (ref "DD1") (pin "B15") (pinfunction "IO_L7N_T1_AD2N_35_B15") (pintype "passive"))
    )
    (net (code "40") (name "/ADC1_D3_P") (class "Default")
      (node (ref "DD1") (pin "C15") (pinfunction "IO_L7P_T1_AD2P_35_C15") (pintype "passive"))
    )
    (net (code "41") (name "/ADC1_D4_N") (class "Default")
      (node (ref "DD1") (pin "B17") (pinfunction "IO_L8N_T1_AD10N_35_B17") (pintype "passive"))
    )
    (net (code "42") (name "/ADC1_D4_P") (class "Default")
      (node (ref "DD1") (pin "B16") (pinfunction "IO_L8P_T1_AD10P_35_B16") (pintype "passive"))
    )
    (net (code "43") (name "/ADC1_D5_N") (class "Default")
      (node (ref "DD1") (pin "A17") (pinfunction "IO_L9N_T1_DQS_AD3N_35_A17") (pintype "passive"))
    )
    (net (code "44") (name "/ADC1_D5_P") (class "Default")
      (node (ref "DD1") (pin "A16") (pinfunction "IO_L9P_T1_DQS_AD3P_35_A16") (pintype "passive"))
    )
    (net (code "45") (name "/ADC1_D6_N") (class "Default")
      (node (ref "DD1") (pin "A19") (pinfunction "IO_L10N_T1_AD11N_35_A19") (pintype "passive"))
    )
    (net (code "46") (name "/ADC1_D6_P") (class "Default")
      (node (ref "DD1") (pin "A18") (pinfunction "IO_L10P_T1_AD11P_35_A18") (pintype "passive"))
    )
    (net (code "47") (name "/ADC1_D7_N") (class "Default")
      (node (ref "DD1") (pin "A22") (pinfunction "IO_L15N_T2_DQS_AD12N_35_A22") (pintype "passive"))
    )
    (net (code "48") (name "/ADC1_D7_P") (class "Default")
      (node (ref "DD1") (pin "A21") (pinfunction "IO_L15P_T2_DQS_AD12P_35_A21") (pintype "passive"))
    )
    (net (code "49") (name "/ADC1_D8_N") (class "Default")
      (node (ref "DD1") (pin "B22") (pinfunction "IO_L18N_T2_AD13N_35_B22") (pintype "passive"))
    )
    (net (code "50") (name "/ADC1_D8_P") (class "Default")
      (node (ref "DD1") (pin "B21") (pinfunction "IO_L18P_T2_AD13P_35_B21") (pintype "passive"))
    )
    (net (code "51") (name "/ADC1_D9_N") (class "Default")
      (node (ref "DD1") (pin "C22") (pinfunction "IO_L16N_T2_35_C22") (pintype "passive"))
    )
    (net (code "52") (name "/ADC1_D9_P") (class "Default")
      (node (ref "DD1") (pin "D22") (pinfunction "IO_L16P_T2_35_D22") (pintype "passive"))
    )
    (net (code "53") (name "/ADC1_D10_N") (class "Default")
      (node (ref "DD1") (pin "D21") (pinfunction "IO_L17N_T2_AD5N_35_D21") (pintype "passive"))
    )
    (net (code "54") (name "/ADC1_D10_P") (class "Default")
      (node (ref "DD1") (pin "E21") (pinfunction "IO_L17P_T2_AD5P_35_E21") (pintype "passive"))
    )
    (net (code "55") (name "/ADC1_D11_N") (class "Default")
      (node (ref "DD1") (pin "F22") (pinfunction "IO_L23N_T3_35_F22") (pintype "passive"))
    )
    (net (code "56") (name "/ADC1_D11_P") (class "Default")
      (node (ref "DD1") (pin "F21") (pinfunction "IO_L23P_T3_35_F21") (pintype "passive"))
    )
    (net (code "57") (name "/ADC1_D12_N") (class "Default")
      (node (ref "DD1") (pin "C20") (pinfunction "IO_L14N_T2_AD4N_SRCC_35_C20") (pintype "passive"))
    )
    (net (code "58") (name "/ADC1_D12_P") (class "Default")
      (node (ref "DD1") (pin "D20") (pinfunction "IO_L14P_T2_AD4P_SRCC_35_D20") (pintype "passive"))
    )
    (net (code "59") (name "/ADC1_D13_N") (class "Default")
      (node (ref "DD1") (pin "G22") (pinfunction "IO_L24N_T3_AD15N_35_G22") (pintype "passive"))
    )
    (net (code "60") (name "/ADC1_D13_P") (class "Default")
      (node (ref "DD1") (pin "H22") (pinfunction "IO_L24P_T3_AD15P_35_H22") (pintype "passive"))
    )
    (net (code "61") (name "/ADC1_D14_N") (class "Default")
      (node (ref "DD1") (pin "E20") (pinfunction "IO_L21N_T3_DQS_AD14N_35_E20") (pintype "passive"))
    )
    (net (code "62") (name "/ADC1_D14_P") (class "Default")
      (node (ref "DD1") (pin "E19") (pinfunction "IO_L21P_T3_DQS_AD14P_35_E19") (pintype "passive"))
    )
    (net (code "63") (name "/ADC1_D15_N") (class "Default")
      (node (ref "DD1") (pin "E18") (pinfunction "IO_L5N_T0_AD9N_35_E18") (pintype "passive"))
    )
    (net (code "64") (name "/ADC1_D15_P") (class "Default")
      (node (ref "DD1") (pin "F18") (pinfunction "IO_L5P_T0_AD9P_35_F18") (pintype "passive"))
    )
    (net (code "65") (name "/CAT_DTR") (class "Default")
      (node (ref "DD1") (pin "W8") (pinfunction "IO_L2N_T0_13_W8") (pintype "passive"))
    )
    (net (code "66") (name "/CAT_RTS") (class "Default")
      (node (ref "DD1") (pin "U10") (pinfunction "IO_L6P_T0_13_U10") (pintype "passive"))
    )
    (net (code "67") (name "/CLKOUT0_N") (class "Default")
      (node (ref "DD1") (pin "M20") (pinfunction "IO_L13N_T2_MRCC_34_M20") (pintype "passive"))
    )
    (net (code "68") (name "/CLKOUT0_P") (class "Default")
      (node (ref "DD1") (pin "M19") (pinfunction "IO_L13P_T2_MRCC_34_M19") (pintype "passive"))
    )
    (net (code "69") (name "/CLKOUT1_N") (class "Default")
      (node (ref "DD1") (pin "B20") (pinfunction "IO_L13N_T2_MRCC_35_B20") (pintype "passive"))
    )
    (net (code "70") (name "/CLKOUT1_P") (class "Default")
      (node (ref "DD1") (pin "B19") (pinfunction "IO_L13P_T2_MRCC_35_B19") (pintype "passive"))
    )
    (net (code "71") (name "/CW_KEY") (class "Default")
      (node (ref "DD1") (pin "V8") (pinfunction "IO_L2P_T0_13_V8") (pintype "passive"))
    )
    (net (code "72") (name "/DAC_D0_N") (class "Default")
      (node (ref "DD1") (pin "V19") (pinfunction "IO_L6N_T0_VREF_33_V19") (pintype "passive"))
    )
    (net (code "73") (name "/DAC_D0_P") (class "Default")
      (node (ref "DD1") (pin "V18") (pinfunction "IO_L6P_T0_33_V18") (pintype "passive"))
    )
    (net (code "74") (name "/DAC_D1_N") (class "Default")
      (node (ref "DD1") (pin "AA14") (pinfunction "IO_L22N_T3_33_AA14") (pintype "passive"))
    )
    (net (code "75") (name "/DAC_D1_P") (class "Default")
      (node (ref "DD1") (pin "Y14") (pinfunction "IO_L22P_T3_33_Y14") (pintype "passive"))
    )
    (net (code "76") (name "/DAC_D2_N") (class "Default")
      (node (ref "DD1") (pin "U16") (pinfunction "IO_L15N_T2_DQS_33_U16") (pintype "passive"))
    )
    (net (code "77") (name "/DAC_D2_P") (class "Default")
      (node (ref "DD1") (pin "U15") (pinfunction "IO_L15P_T2_DQS_33_U15") (pintype "passive"))
    )
    (net (code "78") (name "/DAC_D3_N") (class "Default")
      (node (ref "DD1") (pin "W21") (pinfunction "IO_L4N_T0_33_W21") (pintype "passive"))
    )
    (net (code "79") (name "/DAC_D3_P") (class "Default")
      (node (ref "DD1") (pin "W20") (pinfunction "IO_L4P_T0_33_W20") (pintype "passive"))
    )
    (net (code "80") (name "/DAC_D4_N") (class "Default")
      (node (ref "DD1") (pin "AA13") (pinfunction "IO_L23N_T3_33_AA13") (pintype "passive"))
    )
    (net (code "81") (name "/DAC_D4_P") (class "Default")
      (node (ref "DD1") (pin "Y13") (pinfunction "IO_L23P_T3_33_Y13") (pintype "passive"))
    )
    (net (code "82") (name "/DAC_D5_N") (class "Default")
      (node (ref "DD1") (pin "V17") (pinfunction "IO_L16N_T2_33_V17") (pintype "passive"))
    )
    (net (code "83") (name "/DAC_D5_P") (class "Default")
      (node (ref "DD1") (pin "U17") (pinfunction "IO_L16P_T2_33_U17") (pintype "passive"))
    )
    (net (code "84") (name "/DAC_D6_N") (class "Default")
      (node (ref "DD1") (pin "AB15") (pinfunction "IO_L24N_T3_33_AB15") (pintype "passive"))
    )
    (net (code "85") (name "/DAC_D6_P") (class "Default")
      (node (ref "DD1") (pin "AB14") (pinfunction "IO_L24P_T3_33_AB14") (pintype "passive"))
    )
    (net (code "86") (name "/DAC_D7_N") (class "Default")
      (node (ref "DD1") (pin "AB16") (pinfunction "IO_L18N_T2_33_AB16") (pintype "passive"))
    )
    (net (code "87") (name "/DAC_D7_P") (class "Default")
      (node (ref "DD1") (pin "AA16") (pinfunction "IO_L18P_T2_33_AA16") (pintype "passive"))
    )
    (net (code "88") (name "/DAC_D8_N") (class "Default")
      (node (ref "DD1") (pin "AB17") (pinfunction "IO_L17N_T2_33_AB17") (pintype "passive"))
    )
    (net (code "89") (name "/DAC_D8_P") (class "Default")
      (node (ref "DD1") (pin "AA17") (pinfunction "IO_L17P_T2_33_AA17") (pintype "passive"))
    )
    (net (code "90") (name "/DAC_D9_N") (class "Default")
      (node (ref "DD1") (pin "AB20") (pinfunction "IO_L10N_T1_33_AB20") (pintype "passive"))
    )
    (net (code "91") (name "/DAC_D9_P") (class "Default")
      (node (ref "DD1") (pin "AB19") (pinfunction "IO_L10P_T1_33_AB19") (pintype "passive"))
    )
    (net (code "92") (name "/DAC_D10_N") (class "Default")
      (node (ref "DD1") (pin "AB21") (pinfunction "IO_L8N_T1_33_AB21") (pintype "passive"))
    )
    (net (code "93") (name "/DAC_D10_P") (class "Default")
      (node (ref "DD1") (pin "AA21") (pinfunction "IO_L8P_T1_33_AA21") (pintype "passive"))
    )
    (net (code "94") (name "/DAC_D11_N") (class "Default")
      (node (ref "DD1") (pin "V20") (pinfunction "IO_L5N_T0_33_V20") (pintype "passive"))
    )
    (net (code "95") (name "/DAC_D11_P") (class "Default")
      (node (ref "DD1") (pin "U20") (pinfunction "IO_L5P_T0_33_U20") (pintype "passive"))
    )
    (net (code "96") (name "/DAC_D12_N") (class "Default")
      (node (ref "DD1") (pin "U21") (pinfunction "IO_L1N_T0_33_U21") (pintype "passive"))
    )
    (net (code "97") (name "/DAC_D12_P") (class "Default")
      (node (ref "DD1") (pin "T21") (pinfunction "IO_L1P_T0_33_T21") (pintype "passive"))
    )
    (net (code "98") (name "/DAC_D13_N") (class "Default")
      (node (ref "DD1") (pin "AB22") (pinfunction "IO_L7N_T1_33_AB22") (pintype "passive"))
    )
    (net (code "99") (name "/DAC_D13_P") (class "Default")
      (node (ref "DD1") (pin "AA22") (pinfunction "IO_L7P_T1_33_AA22") (pintype "passive"))
    )
    (net (code "100") (name "/DAC_D14_N") (class "Default")
      (node (ref "DD1") (pin "W22") (pinfunction "IO_L3N_T0_DQS_33_W22") (pintype "passive"))
    )
    (net (code "101") (name "/DAC_D14_P") (class "Default")
      (node (ref "DD1") (pin "V22") (pinfunction "IO_L3P_T0_DQS_33_V22") (pintype "passive"))
    )
    (net (code "102") (name "/DAC_D15_N") (class "Default")
      (node (ref "DD1") (pin "U22") (pinfunction "IO_L2N_T0_33_U22") (pintype "passive"))
    )
    (net (code "103") (name "/DAC_D15_P") (class "Default")
      (node (ref "DD1") (pin "T22") (pinfunction "IO_L2P_T0_33_T22") (pintype "passive"))
    )
    (net (code "104") (name "/DA_N") (class "Default")
      (node (ref "DA12") (pin "14") (pinfunction "MX4+_14") (pintype "passive"))
      (node (ref "XS1") (pin "2") (pinfunction "2_2") (pintype "passive"))
    )
    (net (code "105") (name "/DA_P") (class "Default")
      (node (ref "DA12") (pin "13") (pinfunction "MX4-_13") (pintype "passive"))
      (node (ref "XS1") (pin "1") (pinfunction "1_1") (pintype "passive"))
    )
    (net (code "106") (name "/DB_N") (class "Default")
      (node (ref "DA12") (pin "17") (pinfunction "MX3+_17") (pintype "passive"))
      (node (ref "XS1") (pin "6") (pinfunction "6_6") (pintype "passive"))
    )
    (net (code "107") (name "/DB_P") (class "Default")
      (node (ref "DA12") (pin "16") (pinfunction "MX3-_16") (pintype "passive"))
      (node (ref "XS1") (pin "3") (pinfunction "3_3") (pintype "passive"))
    )
    (net (code "108") (name "/DC_N") (class "Default")
      (node (ref "DA12") (pin "20") (pinfunction "MX2+_20") (pintype "passive"))
      (node (ref "XS1") (pin "5") (pinfunction "5_5") (pintype "passive"))
    )
    (net (code "109") (name "/DC_P") (class "Default")
      (node (ref "DA12") (pin "19") (pinfunction "MX2-_19") (pintype "passive"))
      (node (ref "XS1") (pin "4") (pinfunction "4_4") (pintype "passive"))
    )
    (net (code "110") (name "/DD_N") (class "Default")
      (node (ref "DA12") (pin "23") (pinfunction "MX1+_23") (pintype "passive"))
      (node (ref "XS1") (pin "8") (pinfunction "8_8") (pintype "passive"))
    )
    (net (code "111") (name "/DD_P") (class "Default")
      (node (ref "DA12") (pin "22") (pinfunction "MX1-_22") (pintype "passive"))
      (node (ref "XS1") (pin "7") (pinfunction "7_7") (pintype "passive"))
    )
    (net (code "112") (name "/DIS_RS422_RX") (class "Default")
      (node (ref "DD1") (pin "AA6") (pinfunction "IO_L14N_T2_SRCC_13_AA6") (pintype "passive"))
    )
    (net (code "113") (name "/DIS_RS422_TX") (class "Default")
      (node (ref "DD1") (pin "AB4") (pinfunction "IO_L16N_T2_13_AB4") (pintype "passive"))
    )
    (net (code "114") (name "/ETH0_LEDGRN") (class "Default")
      (node (ref "DD7") (pin "17") (pinfunction "LED1/PME_N1/PHYAD0_17") (pintype "bidirectional"))
      (node (ref "R81") (pin "2") (pinfunction "2_2") (pintype "passive"))
    )
    (net (code "115") (name "/ETH0_LEDYEL") (class "Default")
      (node (ref "DD7") (pin "15") (pinfunction "LED2/PHYAD1_15") (pintype "bidirectional"))
      (node (ref "R83") (pin "2") (pinfunction "2_2") (pintype "passive"))
    )
    (net (code "116") (name "/ETH0_TD0_N") (class "Default")
      (node (ref "DA12") (pin "11") (pinfunction "TD4+_11") (pintype "passive"))
      (node (ref "DD7") (pin "3") (pinfunction "TXRXM_A_3") (pintype "bidirectional"))
    )
    (net (code "117") (name "/ETH0_TD0_P") (class "Default")
      (node (ref "DA12") (pin "12") (pinfunction "TD4-_12") (pintype "passive"))
      (node (ref "DD7") (pin "2") (pinfunction "TXRXP_A_2") (pintype "bidirectional"))
    )
    (net (code "118") (name "/ETH0_TD1_N") (class "Default")
      (node (ref "DA12") (pin "8") (pinfunction "TD3+_8") (pintype "passive"))
      (node (ref "DD7") (pin "6") (pinfunction "TXRXM_B_6") (pintype "bidirectional"))
    )
    (net (code "119") (name "/ETH0_TD1_P") (class "Default")
      (node (ref "DA12") (pin "9") (pinfunction "TD3-_9") (pintype "passive"))
      (node (ref "DD7") (pin "5") (pinfunction "TXRXP_B_5") (pintype "bidirectional"))
    )
    (net (code "120") (name "/ETH0_TD2_N") (class "Default")
      (node (ref "DA12") (pin "5") (pinfunction "TD2+_5") (pintype "passive"))
      (node (ref "DD7") (pin "8") (pinfunction "TXRXM_C_8") (pintype "bidirectional"))
    )
    (net (code "121") (name "/ETH0_TD2_P") (class "Default")
      (node (ref "DA12") (pin "6") (pinfunction "TD2-_6") (pintype "passive"))
      (node (ref "DD7") (pin "7") (pinfunction "TXRXP_C_7") (pintype "bidirectional"))
    )
    (net (code "122") (name "/ETH0_TD3_N") (class "Default")
      (node (ref "DA12") (pin "2") (pinfunction "TD1+_2") (pintype "passive"))
      (node (ref "DD7") (pin "11") (pinfunction "TXRXM_D_11") (pintype "bidirectional"))
    )
    (net (code "123") (name "/ETH0_TD3_P") (class "Default")
      (node (ref "DA12") (pin "3") (pinfunction "TD1-_3") (pintype "passive"))
      (node (ref "DD7") (pin "10") (pinfunction "TXRXP_D_10") (pintype "bidirectional"))
    )
    (net (code "124") (name "/ETH_INT") (class "Default")
      (node (ref "DD1") (pin "AB1") (pinfunction "IO_L15N_T2_DQS_13_AB1") (pintype "passive"))
      (node (ref "DD7") (pin "38") (pinfunction "INT_N/PME_N2_38") (pintype "output"))
    )
    (net (code "125") (name "/ETH_MDC") (class "Default")
      (node (ref "DD1") (pin "AB2") (pinfunction "IO_L15P_T2_DQS_13_AB2") (pintype "passive"))
      (node (ref "DD7") (pin "36") (pinfunction "MDC_36") (pintype "input"))
      (node (ref "R79") (pin "1") (pinfunction "1_1") (pintype "passive"))
    )
    (net (code "126") (name "/ETH_MDIO") (class "Default")
      (node (ref "DD1") (pin "Y4") (pinfunction "IO_L18P_T2_13_Y4") (pintype "passive"))
      (node (ref "DD7") (pin "37") (pinfunction "MDIO_37") (pintype "bidirectional"))
      (node (ref "R78") (pin "1") (pinfunction "1_1") (pintype "passive"))
    )
    (net (code "127") (name "/ETH_RST") (class "Default")
      (node (ref "C155") (pin "2") (pinfunction "2_2") (pintype "passive"))
      (node (ref "DD1") (pin "U11") (pinfunction "IO_L5N_T0_13_U11") (pintype "passive"))
      (node (ref "DD7") (pin "42") (pinfunction "RESET_N_42") (pintype "input"))
      (node (ref "R70") (pin "1") (pinfunction "1_1") (pintype "passive"))
    )
    (net (code "128") (name "/ETH_RXC") (class "Default")
      (node (ref "DD7") (pin "35") (pinfunction "RX_CLK/PHYAD2_35") (pintype "bidirectional"))
      (node (ref "R60") (pin "1") (pinfunction "1_1") (pintype "passive"))
      (node (ref "R75") (pin "1") (pinfunction "1_1") (pintype "passive"))
    )
    (net (code "129") (name "/ETH_RXCTL") (class "Default")
      (node (ref "DD7") (pin "33") (pinfunction "RX_DV/CLK125_EN_33") (pintype "bidirectional"))
      (node (ref "R65") (pin "1") (pinfunction "1_1") (pintype "passive"))
      (node (ref "R76") (pin "1") (pinfunction "1_1") (pintype "passive"))
    )
    (net (code "130") (name "/ETH_RXD0") (class "Default")
      (node (ref "DD7") (pin "32") (pinfunction "RXD0/MODE0_32") (pintype "bidirectional"))
      (node (ref "R66") (pin "2") (pinfunction "2_2") (pintype "passive"))
      (node (ref "R71") (pin "1") (pinfunction "1_1") (pintype "passive"))
    )
    (net (code "131") (name "/ETH_RXD1") (class "Default")
      (node (ref "DD7") (pin "31") (pinfunction "RXD1/MODE1_31") (pintype "bidirectional"))
      (node (ref "R67") (pin "2") (pinfunction "2_2") (pintype "passive"))
      (node (ref "R72") (pin "1") (pinfunction "1_1") (pintype "passive"))
    )
    (net (code "132") (name "/ETH_RXD2") (class "Default")
      (node (ref "DD7") (pin "28") (pinfunction "RXD2/MODE2_28") (pintype "bidirectional"))
      (node (ref "R68") (pin "1") (pinfunction "1_1") (pintype "passive"))
      (node (ref "R73") (pin "1") (pinfunction "1_1") (pintype "passive"))
    )
    (net (code "133") (name "/ETH_RXD3") (class "Default")
      (node (ref "DD7") (pin "27") (pinfunction "RXD3/MODE3_27") (pintype "bidirectional"))
      (node (ref "R69") (pin "1") (pinfunction "1_1") (pintype "passive"))
      (node (ref "R74") (pin "1") (pinfunction "1_1") (pintype "passive"))
    )
    (net (code "134") (name "/ETH_TXC") (class "Default")
      (node (ref "DD1") (pin "AA11") (pinfunction "IO_L8P_T1_13_AA11") (pintype "passive"))
      (node (ref "DD7") (pin "24") (pinfunction "GTX_CLK_24") (pintype "input"))
    )
    (net (code "135") (name "/ETH_TXCTL") (class "Default")
      (node (ref "DD1") (pin "AB10") (pinfunction "IO_L9P_T1_DQS_13_AB10") (pintype "passive"))
      (node (ref "DD7") (pin "25") (pinfunction "TX_EN_25") (pintype "input"))
    )
    (net (code "136") (name "/ETH_TXD0") (class "Default")
      (node (ref "DD1") (pin "Y5") (pinfunction "IO_L13N_T2_MRCC_13_Y5") (pintype "passive"))
      (node (ref "DD7") (pin "19") (pinfunction "TXD0_19") (pintype "input"))
    )
    (net (code "137") (name "/ETH_TXD1") (class "Default")
      (node (ref "DD1") (pin "AA12") (pinfunction "IO_L7P_T1_13_AA12") (pintype "passive"))
      (node (ref "DD7") (pin "20") (pinfunction "TXD1_20") (pintype "input"))
    )
    (net (code "138") (name "/ETH_TXD2") (class "Default")
      (node (ref "DD1") (pin "AB12") (pinfunction "IO_L7N_T1_13_AB12") (pintype "passive"))
      (node (ref "DD7") (pin "21") (pinfunction "TXD2_21") (pintype "input"))
    )
    (net (code "139") (name "/ETH_TXD3") (class "Default")
      (node (ref "DD1") (pin "AB11") (pinfunction "IO_L8N_T1_13_AB11") (pintype "passive"))
      (node (ref "DD7") (pin "22") (pinfunction "TXD3_22") (pintype "input"))
    )
    (net (code "140") (name "/I2S1BCLK") (class "Default")
      (node (ref "DD1") (pin "AA4") (pinfunction "IO_L18N_T2_13_AA4") (pintype "passive"))
    )
    (net (code "141") (name "/I2S1DATA0") (class "Default")
      (node (ref "DD1") (pin "W6") (pinfunction "IO_L24P_T3_13_W6") (pintype "passive"))
    )
    (net (code "142") (name "/I2S1DATA1") (class "Default")
      (node (ref "DD1") (pin "W5") (pinfunction "IO_L24N_T3_13_W5") (pintype "passive"))
    )
    (net (code "143") (name "/I2S1MCLK") (class "Default")
      (node (ref "DD1") (pin "Y9") (pinfunction "IO_L12P_T1_MRCC_13_Y9") (pintype "passive"))
    )
    (net (code "144") (name "/I2S1WCLK") (class "Default")
      (node (ref "DD1") (pin "Y6") (pinfunction "IO_L13P_T2_MRCC_13_Y6") (pintype "passive"))
    )
    (net (code "145") (name "/PTT") (class "Default")
      (node (ref "DD1") (pin "V9") (pinfunction "IO_L1N_T0_13_V9") (pintype "passive"))
    )
    (net (code "146") (name "/PUDC_B") (class "Default")
      (node (ref "DD1") (pin "K16") (pinfunction "IO_L3P_T0_DQS_PUDC_B_34_K16") (pintype "passive"))
      (node (ref "R61") (pin "1") (pinfunction "1_1") (pintype "passive"))
    )
    (net (code "147") (name "/RS422_RX") (class "Default")
      (node (ref "DD1") (pin "Y8") (pinfunction "IO_L12N_T1_MRCC_13_Y8") (pintype "passive"))
    )
    (net (code "148") (name "/RS422_TX") (class "Default")
      (node (ref "DD1") (pin "W7") (pinfunction "IO_L23N_T3_13_W7") (pintype "passive"))
    )
    (net (code "149") (name "/SERCLK_N") (class "Default")
      (node (ref "DD1") (pin "T18") (pinfunction "IO_L23N_T3_34_T18") (pintype "passive"))
      (node (ref "XS4") (pin "5") (pinfunction "5_5") (pintype "passive"))
    )
    (net (code "150") (name "/SERCLK_P") (class "Default")
      (node (ref "DD1") (pin "R18") (pinfunction "IO_L23P_T3_34_R18") (pintype "passive"))
      (node (ref "XS4") (pin "6") (pinfunction "6_6") (pintype "passive"))
    )
    (net (code "151") (name "/SERDATA_N") (class "Default")
      (node (ref "DD1") (pin "W13") (pinfunction "IO_L20N_T3_33_W13") (pintype "passive"))
      (node (ref "XS4") (pin "3") (pinfunction "3_3") (pintype "passive"))
    )
    (net (code "152") (name "/SERDATA_P") (class "Default")
      (node (ref "DD1") (pin "V13") (pinfunction "IO_L20P_T3_33_V13") (pintype "passive"))
      (node (ref "XS4") (pin "2") (pinfunction "2_2") (pintype "passive"))
    )
    (net (code "153") (name "/TX_FAIL") (class "Default")
      (node (ref "DD1") (pin "V7") (pinfunction "IO_L23P_T3_13_V7") (pintype "passive"))
    )
    (net (code "154") (name "/TX_ON") (class "Default")
      (node (ref "DD1") (pin "V5") (pinfunction "IO_L21P_T3_DQS_13_V5") (pintype "passive"))
    )
    (net (code "155") (name "DAC_DCI_N") (class "Default")
      (node (ref "DD1") (pin "Y16") (pinfunction "IO_L14N_T2_SRCC_33_Y16") (pintype "passive"))
    )
    (net (code "156") (name "DAC_DCI_P") (class "Default")
      (node (ref "DD1") (pin "W16") (pinfunction "IO_L14P_T2_SRCC_33_W16") (pintype "passive"))
    )
    (net (code "157") (name "DAC_DCO_N") (class "Default")
      (node (ref "DD1") (pin "AA19") (pinfunction "IO_L11N_T1_SRCC_33_AA19") (pintype "passive"))
    )
    (net (code "158") (name "DAC_DCO_P") (class "Default")
      (node (ref "DD1") (pin "Y19") (pinfunction "IO_L11P_T1_SRCC_33_Y19") (pintype "passive"))
    )
    (net (code "159") (name "ETH0_1V2") (class "Default")
      (node (ref "C131") (pin "2") (pinfunction "2_2") (pintype "passive"))
      (node (ref "L16") (pin "2") (pinfunction "2_2") (pintype "passive"))
      (node (ref "L19") (pin "1") (pinfunction "1_1") (pintype "passive"))
      (node (ref "L20") (pin "1") (pinfunction "1_1") (pintype "passive"))
      (node (ref "L21") (pin "1") (pinfunction "1_1") (pintype "passive"))
      (node (ref "R63") (pin "2") (pinfunction "2_2") (pintype "passive"))
    )
    (net (code "160") (name "ETH0_3V3") (class "Default")
      (node (ref "C146") (pin "2") (pinfunction "2_2") (pintype "passive"))
      (node (ref "DA11") (pin "7") (pinfunction "EN_7") (pintype "input"))
      (node (ref "L17") (pin "2") (pinfunction "2_2") (pintype "passive"))
      (node (ref "L18") (pin "1") (pinfunction "1_1") (pintype "passive"))
      (node (ref "R62") (pin "2") (pinfunction "2_2") (pintype "passive"))
      (node (ref "R71") (pin "2") (pinfunction "2_2") (pintype "passive"))
      (node (ref "R72") (pin "2") (pinfunction "2_2") (pintype "passive"))
      (node (ref "R73") (pin "2") (pinfunction "2_2") (pintype "passive"))
      (node (ref "R74") (pin "2") (pinfunction "2_2") (pintype "passive"))
      (node (ref "R75") (pin "2") (pinfunction "2_2") (pintype "passive"))
      (node (ref "R77") (pin "2") (pinfunction "2_2") (pintype "passive"))
      (node (ref "R78") (pin "2") (pinfunction "2_2") (pintype "passive"))
      (node (ref "R79") (pin "2") (pinfunction "2_2") (pintype "passive"))
      (node (ref "R81") (pin "1") (pinfunction "1_1") (pintype "passive"))
      (node (ref "R83") (pin "1") (pinfunction "1_1") (pintype "passive"))
    )
    (net (code "161") (name "GND") (class "Default")
      (node (ref "C128") (pin "1") (pinfunction "1_1") (pintype "passive"))
      (node (ref "C129") (pin "1") (pinfunction "1_1") (pintype "passive"))
      (node (ref "C131") (pin "1") (pinfunction "1_1") (pintype "passive"))
      (node (ref "C132") (pin "1") (pinfunction "1_1") (pintype "passive"))
      (node (ref "C133") (pin "1") (pinfunction "1_1") (pintype "passive"))
      (node (ref "C134") (pin "1") (pinfunction "1_1") (pintype "passive"))
      (node (ref "C135") (pin "1") (pinfunction "1_1") (pintype "passive"))
      (node (ref "C136") (pin "1") (pinfunction "1_1") (pintype "passive"))
      (node (ref "C138") (pin "1") (pinfunction "1_1") (pintype "passive"))
      (node (ref "C139") (pin "1") (pinfunction "1_1") (pintype "passive"))
      (node (ref "C140") (pin "1") (pinfunction "1_1") (pintype "passive"))
      (node (ref "C142") (pin "1") (pinfunction "1_1") (pintype "passive"))
      (node (ref "C143") (pin "1") (pinfunction "1_1") (pintype "passive"))
      (node (ref "C144") (pin "1") (pinfunction "1_1") (pintype "passive"))
      (node (ref "C145") (pin "1") (pinfunction "1_1") (pintype "passive"))
      (node (ref "C146") (pin "1") (pinfunction "1_1") (pintype "passive"))
      (node (ref "C147") (pin "1") (pinfunction "1_1") (pintype "passive"))
      (node (ref "C148") (pin "1") (pinfunction "1_1") (pintype "passive"))
      (node (ref "C149") (pin "1") (pinfunction "1_1") (pintype "passive"))
      (node (ref "C150") (pin "1") (pinfunction "1_1") (pintype "passive"))
      (node (ref "C151") (pin "1") (pinfunction "1_1") (pintype "passive"))
      (node (ref "C152") (pin "1") (pinfunction "1_1") (pintype "passive"))
      (node (ref "C153") (pin "1") (pinfunction "1_1") (pintype "passive"))
      (node (ref "C154") (pin "1") (pinfunction "1_1") (pintype "passive"))
      (node (ref "C155") (pin "1") (pinfunction "1_1") (pintype "passive"))
      (node (ref "C156") (pin "1") (pinfunction "1_1") (pintype "passive"))
      (node (ref "C157") (pin "1") (pinfunction "1_1") (pintype "passive"))
      (node (ref "C158") (pin "1") (pinfunction "1_1") (pintype "passive"))
      (node (ref "C159") (pin "1") (pinfunction "1_1") (pintype "passive"))
      (node (ref "C160") (pin "1") (pinfunction "1_1") (pintype "passive"))
      (node (ref "C161") (pin "1") (pinfunction "1_1") (pintype "passive"))
      (node (ref "C162") (pin "1") (pinfunction "1_1") (pintype "passive"))
      (node (ref "C163") (pin "1") (pinfunction "1_1") (pintype "passive"))
      (node (ref "C164") (pin "1") (pinfunction "1_1") (pintype "passive"))
      (node (ref "C165") (pin "1") (pinfunction "1_1") (pintype "passive"))
      (node (ref "C166") (pin "1") (pinfunction "1_1") (pintype "passive"))
      (node (ref "C167") (pin "1") (pinfunction "1_1") (pintype "passive"))
      (node (ref "C168") (pin "1") (pinfunction "1_1") (pintype "passive"))
      (node (ref "C169") (pin "1") (pinfunction "1_1") (pintype "passive"))
      (node (ref "C170") (pin "1") (pinfunction "1_1") (pintype "passive"))
      (node (ref "C171") (pin "1") (pinfunction "1_1") (pintype "passive"))
      (node (ref "C172") (pin "1") (pinfunction "1_1") (pintype "passive"))
      (node (ref "C173") (pin "2") (pinfunction "2_2") (pintype "passive"))
      (node (ref "C174") (pin "1") (pinfunction "1_1") (pintype "passive"))
      (node (ref "C175") (pin "1") (pinfunction "1_1") (pintype "passive"))
      (node (ref "C176") (pin "1") (pinfunction "1_1") (pintype "passive"))
      (node (ref "C177") (pin "1") (pinfunction "1_1") (pintype "passive"))
      (node (ref "C178") (pin "1") (pinfunction "1_1") (pintype "passive"))
      (node (ref "C179") (pin "1") (pinfunction "1_1") (pintype "passive"))
      (node (ref "C180") (pin "1") (pinfunction "1_1") (pintype "passive"))
      (node (ref "C181") (pin "2") (pinfunction "2_2") (pintype "passive"))
      (node (ref "DA11") (pin "1") (pinfunction "GND_1") (pintype "passive"))
      (node (ref "DD7") (pin "29") (pinfunction "VSS_29") (pintype "passive"))
      (node (ref "DD7") (pin "49") (pinfunction "P_GND_49") (pintype "passive"))
      (node (ref "R64") (pin "2") (pinfunction "2_2") (pintype "passive"))
      (node (ref "R76") (pin "2") (pinfunction "2_2") (pintype "passive"))
      (node (ref "R80") (pin "2") (pinfunction "2_2") (pintype "passive"))
      (node (ref "R87") (pin "2") (pinfunction "2_2") (pintype "passive"))
      (node (ref "XS4") (pin "1") (pinfunction "1_1") (pintype "passive"))
      (node (ref "XS4") (pin "4") (pinfunction "4_4") (pintype "passive"))
      (node (ref "XS4") (pin "7") (pinfunction "7_7") (pintype "passive"))
    )
    (net (code "162") (name "Net-(BQ1-OSC1)") (class "Default")
      (node (ref "BQ1") (pin "1") (pinfunction "OSC1_1") (pintype "passive"))
      (node (ref "C175") (pin "2") (pinfunction "2_2") (pintype "passive"))
      (node (ref "DD7") (pin "46") (pinfunction "XI_46") (pintype "input"))
    )
    (net (code "163") (name "Net-(BQ1-OSC2)") (class "Default")
      (node (ref "BQ1") (pin "3") (pinfunction "OSC2_3") (pintype "passive"))
      (node (ref "C176") (pin "2") (pinfunction "2_2") (pintype "passive"))
      (node (ref "DD7") (pin "45") (pinfunction "XO_45") (pintype "output"))
    )
    (net (code "164") (name "Net-(C166-Pad2)") (class "Default")
      (node (ref "C166") (pin "2") (pinfunction "2_2") (pintype "passive"))
      (node (ref "C167") (pin "2") (pinfunction "2_2") (pintype "passive"))
      (node (ref "C168") (pin "2") (pinfunction "2_2") (pintype "passive"))
      (node (ref "C170") (pin "2") (pinfunction "2_2") (pintype "passive"))
      (node (ref "DD7") (pin "1") (pinfunction "AVDDH_1") (pintype "power_in"))
      (node (ref "DD7") (pin "12") (pinfunction "AVDDH_12") (pintype "power_in"))
      (node (ref "DD7") (pin "16") (pinfunction "DVDDH_16") (pintype "power_in"))
      (node (ref "DD7") (pin "34") (pinfunction "DVDDH_34") (pintype "power_in"))
      (node (ref "DD7") (pin "40") (pinfunction "DVDDH_40") (pintype "power_in"))
      (node (ref "L18") (pin "2") (pinfunction "2_2") (pintype "passive"))
    )
    (net (code "165") (name "Net-(C169-Pad2)") (class "Default")
      (node (ref "C169") (pin "2") (pinfunction "2_2") (pintype "passive"))
      (node (ref "C171") (pin "2") (pinfunction "2_2") (pintype "passive"))
      (node (ref "C172") (pin "2") (pinfunction "2_2") (pintype "passive"))
      (node (ref "C177") (pin "2") (pinfunction "2_2") (pintype "passive"))
      (node (ref "DD7") (pin "14") (pinfunction "DVDDL_14") (pintype "power_in"))
      (node (ref "DD7") (pin "18") (pinfunction "DVDDL_18") (pintype "power_in"))
      (node (ref "DD7") (pin "23") (pinfunction "DVDDL_23") (pintype "power_in"))
      (node (ref "DD7") (pin "26") (pinfunction "DVDDL_26") (pintype "power_in"))
      (node (ref "DD7") (pin "30") (pinfunction "DVDDL_30") (pintype "power_in"))
      (node (ref "DD7") (pin "39") (pinfunction "DVDDL_39") (pintype "power_in"))
      (node (ref "L19") (pin "2") (pinfunction "2_2") (pintype "passive"))
    )
    (net (code "166") (name "Net-(C173-Pad1)") (class "Default")
      (node (ref "C173") (pin "1") (pinfunction "1_1") (pintype "passive"))
      (node (ref "R82") (pin "2") (pinfunction "2_2") (pintype "passive"))
      (node (ref "R84") (pin "2") (pinfunction "2_2") (pintype "passive"))
      (node (ref "R85") (pin "2") (pinfunction "2_2") (pintype "passive"))
      (node (ref "R86") (pin "2") (pinfunction "2_2") (pintype "passive"))
    )
    (net (code "167") (name "Net-(C174-Pad2)") (class "Default")
      (node (ref "C174") (pin "2") (pinfunction "2_2") (pintype "passive"))
      (node (ref "C179") (pin "2") (pinfunction "2_2") (pintype "passive"))
      (node (ref "DD7") (pin "4") (pinfunction "AVDDL_4") (pintype "power_in"))
      (node (ref "DD7") (pin "9") (pinfunction "AVDDL_9") (pintype "power_in"))
      (node (ref "L20") (pin "2") (pinfunction "2_2") (pintype "passive"))
    )
    (net (code "168") (name "Net-(C181-Pad1)") (class "Default")
      (node (ref "C181") (pin "1") (pinfunction "1_1") (pintype "passive"))
      (node (ref "R87") (pin "1") (pinfunction "1_1") (pintype "passive"))
      (node (ref "XS1") (pin "9") (pinfunction "9_9") (pintype "passive"))
    )
    (net (code "169") (name "Net-(DA11-SS)") (class "Default")
      (node (ref "C129") (pin "2") (pinfunction "2_2") (pintype "passive"))
      (node (ref "DA11") (pin "5") (pinfunction "SS_5") (pintype "passive"))
    )
    (net (code "170") (name "Net-(DA11-SW)") (class "Default")
      (node (ref "C130") (pin "1") (pinfunction "1_1") (pintype "passive"))
      (node (ref "DA11") (pin "2") (pinfunction "SW_2") (pintype "passive"))
      (node (ref "L16") (pin "1") (pinfunction "1_1") (pintype "passive"))
    )
    (net (code "171") (name "Net-(DA11-VBST)") (class "Default")
      (node (ref "C130") (pin "2") (pinfunction "2_2") (pintype "passive"))
      (node (ref "DA11") (pin "8") (pinfunction "VBST_8") (pintype "passive"))
    )
    (net (code "172") (name "Net-(DA11-VFB)") (class "Default")
      (node (ref "DA11") (pin "6") (pinfunction "VFB_6") (pintype "passive"))
      (node (ref "R63") (pin "1") (pinfunction "1_1") (pintype "passive"))
      (node (ref "R64") (pin "1") (pinfunction "1_1") (pintype "passive"))
    )
    (net (code "173") (name "Net-(DA12-MCT1)") (class "Default")
      (node (ref "DA12") (pin "24") (pinfunction "MCT1_24") (pintype "passive"))
      (node (ref "R86") (pin "1") (pinfunction "1_1") (pintype "passive"))
    )
    (net (code "174") (name "Net-(DA12-MCT2)") (class "Default")
      (node (ref "DA12") (pin "21") (pinfunction "MCT2_21") (pintype "passive"))
      (node (ref "R85") (pin "1") (pinfunction "1_1") (pintype "passive"))
    )
    (net (code "175") (name "Net-(DA12-MCT3)") (class "Default")
      (node (ref "DA12") (pin "18") (pinfunction "MCT3_18") (pintype "passive"))
      (node (ref "R84") (pin "1") (pinfunction "1_1") (pintype "passive"))
    )
    (net (code "176") (name "Net-(DA12-MCT4)") (class "Default")
      (node (ref "DA12") (pin "15") (pinfunction "MCT4_15") (pintype "passive"))
      (node (ref "R82") (pin "1") (pinfunction "1_1") (pintype "passive"))
    )
    (net (code "177") (name "Net-(DA12-TCT1)") (class "Default")
      (node (ref "C162") (pin "2") (pinfunction "2_2") (pintype "passive"))
      (node (ref "DA12") (pin "1") (pinfunction "TCT1_1") (pintype "passive"))
    )
    (net (code "178") (name "Net-(DA12-TCT2)") (class "Default")
      (node (ref "C163") (pin "2") (pinfunction "2_2") (pintype "passive"))
      (node (ref "DA12") (pin "4") (pinfunction "TCT2_4") (pintype "passive"))
    )
    (net (code "179") (name "Net-(DA12-TCT3)") (class "Default")
      (node (ref "C164") (pin "2") (pinfunction "2_2") (pintype "passive"))
      (node (ref "DA12") (pin "7") (pinfunction "TCT3_7") (pintype "passive"))
    )
    (net (code "180") (name "Net-(DA12-TCT4)") (class "Default")
      (node (ref "C165") (pin "2") (pinfunction "2_2") (pintype "passive"))
      (node (ref "DA12") (pin "10") (pinfunction "TCT4_10") (pintype "passive"))
    )
    (net (code "181") (name "Net-(DD1B-IO_L9N_T1_DQS_13)") (class "Default")
      (node (ref "DD1") (pin "AB9") (pinfunction "IO_L9N_T1_DQS_13_AB9") (pintype "passive"))
      (node (ref "R69") (pin "2") (pinfunction "2_2") (pintype "passive"))
    )
    (net (code "182") (name "Net-(DD1B-IO_L10P_T1_13)") (class "Default")
      (node (ref "DD1") (pin "Y11") (pinfunction "IO_L10P_T1_13_Y11") (pintype "passive"))
      (node (ref "R68") (pin "2") (pinfunction "2_2") (pintype "passive"))
    )
    (net (code "183") (name "Net-(DD1B-IO_L14P_T2_SRCC_13)") (class "Default")
      (node (ref "DD1") (pin "AA7") (pinfunction "IO_L14P_T2_SRCC_13_AA7") (pintype "passive"))
      (node (ref "R60") (pin "2") (pinfunction "2_2") (pintype "passive"))
    )
    (net (code "184") (name "Net-(DD1B-IO_L16P_T2_13)") (class "Default")
      (node (ref "DD1") (pin "AB5") (pinfunction "IO_L16P_T2_13_AB5") (pintype "passive"))
      (node (ref "R65") (pin "2") (pinfunction "2_2") (pintype "passive"))
    )
    (net (code "185") (name "Net-(DD1B-IO_L17N_T2_13)") (class "Default")
      (node (ref "DD1") (pin "AB6") (pinfunction "IO_L17N_T2_13_AB6") (pintype "passive"))
      (node (ref "R66") (pin "1") (pinfunction "1_1") (pintype "passive"))
    )
    (net (code "186") (name "Net-(DD1B-IO_L17P_T2_13)") (class "Default")
      (node (ref "DD1") (pin "AB7") (pinfunction "IO_L17P_T2_13_AB7") (pintype "passive"))
      (node (ref "R67") (pin "1") (pinfunction "1_1") (pintype "passive"))
    )
    (net (code "187") (name "Net-(DD1C-IO_L19P_T3_33)") (class "Default")
      (node (ref "DD1") (pin "V14") (pinfunction "IO_L19P_T3_33_V14") (pintype "passive"))
      (node (ref "X4") (pin "1") (pinfunction "~_1") (pintype "passive"))
    )
    (net (code "188") (name "Net-(DD1D-IO_L21P_T3_DQS_34)") (class "Default")
      (node (ref "DD1") (pin "T16") (pinfunction "IO_L21P_T3_DQS_34_T16") (pintype "passive"))
      (node (ref "X3") (pin "1") (pinfunction "~_1") (pintype "passive"))
    )
    (net (code "189") (name "Net-(DD7A-CLK125_NDO{slash}LED_MODE)") (class "Default")
      (node (ref "DD7") (pin "41") (pinfunction "CLK125_NDO/LED_MODE_41") (pintype "bidirectional"))
      (node (ref "R77") (pin "1") (pinfunction "1_1") (pintype "passive"))
    )
    (net (code "190") (name "Net-(DD7A-ISET)") (class "Default")
      (node (ref "DD7") (pin "48") (pinfunction "ISET_48") (pintype "bidirectional"))
      (node (ref "R80") (pin "1") (pinfunction "1_1") (pintype "passive"))
    )
    (net (code "191") (name "Net-(DD7B-AVDDL_PLL)") (class "Default")
      (node (ref "C178") (pin "2") (pinfunction "2_2") (pintype "passive"))
      (node (ref "C180") (pin "2") (pinfunction "2_2") (pintype "passive"))
      (node (ref "DD7") (pin "44") (pinfunction "AVDDL_PLL_44") (pintype "power_in"))
      (node (ref "L21") (pin "2") (pinfunction "2_2") (pintype "passive"))
    )
    (net (code "192") (name "PG_ETH0") (class "Default")
      (node (ref "DA11") (pin "4") (pinfunction "PG_4") (pintype "open_collector"))
      (node (ref "R62") (pin "1") (pinfunction "1_1") (pintype "passive"))
      (node (ref "R70") (pin "2") (pinfunction "2_2") (pintype "passive"))
    )
    (net (code "193") (name "VCC_12V0") (class "Default")
      (node (ref "C128") (pin "2") (pinfunction "2_2") (pintype "passive"))
      (node (ref "DA11") (pin "3") (pinfunction "VIN_3") (pintype "passive"))
    )
    (net (code "194") (name "VDD_2V5") (class "Default")
      (node (ref "C134") (pin "2") (pinfunction "2_2") (pintype "passive"))
      (node (ref "C135") (pin "2") (pinfunction "2_2") (pintype "passive"))
      (node (ref "C138") (pin "2") (pinfunction "2_2") (pintype "passive"))
      (node (ref "C139") (pin "2") (pinfunction "2_2") (pintype "passive"))
      (node (ref "C142") (pin "2") (pinfunction "2_2") (pintype "passive"))
      (node (ref "C143") (pin "2") (pinfunction "2_2") (pintype "passive"))
      (node (ref "C145") (pin "2") (pinfunction "2_2") (pintype "passive"))
      (node (ref "C147") (pin "2") (pinfunction "2_2") (pintype "passive"))
      (node (ref "C148") (pin "2") (pinfunction "2_2") (pintype "passive"))
      (node (ref "C149") (pin "2") (pinfunction "2_2") (pintype "passive"))
      (node (ref "C150") (pin "2") (pinfunction "2_2") (pintype "passive"))
      (node (ref "C151") (pin "2") (pinfunction "2_2") (pintype "passive"))
      (node (ref "C152") (pin "2") (pinfunction "2_2") (pintype "passive"))
      (node (ref "C153") (pin "2") (pinfunction "2_2") (pintype "passive"))
      (node (ref "C154") (pin "2") (pinfunction "2_2") (pintype "passive"))
      (node (ref "C156") (pin "2") (pinfunction "2_2") (pintype "passive"))
      (node (ref "C157") (pin "2") (pinfunction "2_2") (pintype "passive"))
      (node (ref "C158") (pin "2") (pinfunction "2_2") (pintype "passive"))
      (node (ref "C159") (pin "2") (pinfunction "2_2") (pintype "passive"))
      (node (ref "C160") (pin "2") (pinfunction "2_2") (pintype "passive"))
      (node (ref "C161") (pin "2") (pinfunction "2_2") (pintype "passive"))
      (node (ref "DD1") (pin "A20") (pinfunction "VCCO_35_A20") (pintype "passive"))
      (node (ref "DD1") (pin "AA20") (pinfunction "VCCO_33_AA20") (pintype "passive"))
      (node (ref "DD1") (pin "AB13") (pinfunction "VCCO_33_AB13") (pintype "passive"))
      (node (ref "DD1") (pin "C16") (pinfunction "VCCO_35_C16") (pintype "passive"))
      (node (ref "DD1") (pin "D19") (pinfunction "VCCO_35_D19") (pintype "passive"))
      (node (ref "DD1") (pin "E22") (pinfunction "VCCO_35_E22") (pintype "passive"))
      (node (ref "DD1") (pin "F15") (pinfunction "VCCO_35_F15") (pintype "passive"))
      (node (ref "DD1") (pin "G18") (pinfunction "VCCO_35_G18") (pintype "passive"))
      (node (ref "DD1") (pin "H21") (pinfunction "VCCO_35_H21") (pintype "passive"))
      (node (ref "DD1") (pin "K17") (pinfunction "VCCO_34_K17") (pintype "passive"))
      (node (ref "DD1") (pin "L20") (pinfunction "VCCO_34_L20") (pintype "passive"))
      (node (ref "DD1") (pin "N16") (pinfunction "VCCO_34_N16") (pintype "passive"))
      (node (ref "DD1") (pin "P19") (pinfunction "VCCO_34_P19") (pintype "passive"))
      (node (ref "DD1") (pin "R22") (pinfunction "VCCO_34_R22") (pintype "passive"))
      (node (ref "DD1") (pin "T15") (pinfunction "VCCO_34_T15") (pintype "passive"))
      (node (ref "DD1") (pin "U18") (pinfunction "VCCO_33_U18") (pintype "passive"))
      (node (ref "DD1") (pin "V21") (pinfunction "VCCO_33_V21") (pintype "passive"))
      (node (ref "DD1") (pin "W14") (pinfunction "VCCO_33_W14") (pintype "passive"))
      (node (ref "DD1") (pin "Y17") (pinfunction "VCCO_33_Y17") (pintype "passive"))
      (node (ref "R61") (pin "2") (pinfunction "2_2") (pintype "passive"))
    )
    (net (code "195") (name "VDD_3V3") (class "Default")
      (node (ref "C132") (pin "2") (pinfunction "2_2") (pintype "passive"))
      (node (ref "C133") (pin "2") (pinfunction "2_2") (pintype "passive"))
      (node (ref "C136") (pin "2") (pinfunction "2_2") (pintype "passive"))
      (node (ref "C140") (pin "2") (pinfunction "2_2") (pintype "passive"))
      (node (ref "C144") (pin "2") (pinfunction "2_2") (pintype "passive"))
      (node (ref "DD1") (pin "AA10") (pinfunction "VCCO_13_AA10") (pintype "passive"))
      (node (ref "DD1") (pin "AB3") (pinfunction "VCCO_13_AB3") (pintype "passive"))
      (node (ref "DD1") (pin "T5") (pinfunction "VCCO_13_T5") (pintype "passive"))
      (node (ref "DD1") (pin "U8") (pinfunction "VCCO_13_U8") (pintype "passive"))
      (node (ref "DD1") (pin "V11") (pinfunction "VCCO_13_V11") (pintype "passive"))
      (node (ref "DD1") (pin "W4") (pinfunction "VCCO_13_W4") (pintype "passive"))
      (node (ref "DD1") (pin "Y7") (pinfunction "VCCO_13_Y7") (pintype "passive"))
      (node (ref "L17") (pin "1") (pinfunction "1_1") (pintype "passive"))
    )
    (net (code "196") (name "unconnected-(DD1B-IO_0_13-PadR7)") (class "Default")
      (node (ref "DD1") (pin "R7") (pinfunction "IO_0_13_R7") (pintype "passive"))
    )
    (net (code "197") (name "unconnected-(DD1B-IO_25_13-PadU7)") (class "Default")
      (node (ref "DD1") (pin "U7") (pinfunction "IO_25_13_U7") (pintype "passive"))
    )
    (net (code "198") (name "unconnected-(DD1B-IO_L1P_T0_13-PadV10)") (class "Default")
      (node (ref "DD1") (pin "V10") (pinfunction "IO_L1P_T0_13_V10") (pintype "passive"))
    )
    (net (code "199") (name "unconnected-(DD1B-IO_L3N_T0_DQS_13-PadW10)") (class "Default")
      (node (ref "DD1") (pin "W10") (pinfunction "IO_L3N_T0_DQS_13_W10") (pintype "passive"))
    )
    (net (code "200") (name "unconnected-(DD1B-IO_L3P_T0_DQS_13-PadW11)") (class "Default")
      (node (ref "DD1") (pin "W11") (pinfunction "IO_L3P_T0_DQS_13_W11") (pintype "passive"))
    )
    (net (code "201") (name "unconnected-(DD1B-IO_L4N_T0_13-PadW12)") (class "Default")
      (node (ref "DD1") (pin "W12") (pinfunction "IO_L4N_T0_13_W12") (pintype "passive"))
    )
    (net (code "202") (name "unconnected-(DD1B-IO_L4P_T0_13-PadV12)") (class "Default")
      (node (ref "DD1") (pin "V12") (pinfunction "IO_L4P_T0_13_V12") (pintype "passive"))
    )
    (net (code "203") (name "unconnected-(DD1B-IO_L5P_T0_13-PadU12)") (class "Default")
      (node (ref "DD1") (pin "U12") (pinfunction "IO_L5P_T0_13_U12") (pintype "passive"))
    )
    (net (code "204") (name "unconnected-(DD1B-IO_L6N_T0_VREF_13-PadU9)") (class "Default")
      (node (ref "DD1") (pin "U9") (pinfunction "IO_L6N_T0_VREF_13_U9") (pintype "passive"))
    )
    (net (code "205") (name "unconnected-(DD1B-IO_L10N_T1_13-PadY10)") (class "Default")
      (node (ref "DD1") (pin "Y10") (pinfunction "IO_L10N_T1_13_Y10") (pintype "passive"))
    )
    (net (code "206") (name "unconnected-(DD1B-IO_L11N_T1_SRCC_13-PadAA8)") (class "Default")
      (node (ref "DD1") (pin "AA8") (pinfunction "IO_L11N_T1_SRCC_13_AA8") (pintype "passive"))
    )
    (net (code "207") (name "unconnected-(DD1B-IO_L11P_T1_SRCC_13-PadAA9)") (class "Default")
      (node (ref "DD1") (pin "AA9") (pinfunction "IO_L11P_T1_SRCC_13_AA9") (pintype "passive"))
    )
    (net (code "208") (name "unconnected-(DD1B-IO_L19N_T3_VREF_13-PadT6)") (class "Default")
      (node (ref "DD1") (pin "T6") (pinfunction "IO_L19N_T3_VREF_13_T6") (pintype "passive"))
    )
    (net (code "209") (name "unconnected-(DD1B-IO_L19P_T3_13-PadR6)") (class "Default")
      (node (ref "DD1") (pin "R6") (pinfunction "IO_L19P_T3_13_R6") (pintype "passive"))
    )
    (net (code "210") (name "unconnected-(DD1B-IO_L20N_T3_13-PadU4)") (class "Default")
      (node (ref "DD1") (pin "U4") (pinfunction "IO_L20N_T3_13_U4") (pintype "passive"))
    )
    (net (code "211") (name "unconnected-(DD1B-IO_L20P_T3_13-PadT4)") (class "Default")
      (node (ref "DD1") (pin "T4") (pinfunction "IO_L20P_T3_13_T4") (pintype "passive"))
    )
    (net (code "212") (name "unconnected-(DD1B-IO_L21N_T3_DQS_13-PadV4)") (class "Default")
      (node (ref "DD1") (pin "V4") (pinfunction "IO_L21N_T3_DQS_13_V4") (pintype "passive"))
    )
    (net (code "213") (name "unconnected-(DD1B-IO_L22N_T3_13-PadU5)") (class "Default")
      (node (ref "DD1") (pin "U5") (pinfunction "IO_L22N_T3_13_U5") (pintype "passive"))
    )
    (net (code "214") (name "unconnected-(DD1B-IO_L22P_T3_13-PadU6)") (class "Default")
      (node (ref "DD1") (pin "U6") (pinfunction "IO_L22P_T3_13_U6") (pintype "passive"))
    )
    (net (code "215") (name "unconnected-(DD1C-IO_0_33-PadU19)") (class "Default")
      (node (ref "DD1") (pin "U19") (pinfunction "IO_0_33_U19") (pintype "passive"))
    )
    (net (code "216") (name "unconnected-(DD1C-IO_25_33-PadU14)") (class "Default")
      (node (ref "DD1") (pin "U14") (pinfunction "IO_25_33_U14") (pintype "passive"))
    )
    (net (code "217") (name "unconnected-(DD1C-IO_L9N_T1_DQS_33-PadY21)") (class "Default")
      (node (ref "DD1") (pin "Y21") (pinfunction "IO_L9N_T1_DQS_33_Y21") (pintype "passive"))
    )
    (net (code "218") (name "unconnected-(DD1C-IO_L9P_T1_DQS_33-PadY20)") (class "Default")
      (node (ref "DD1") (pin "Y20") (pinfunction "IO_L9P_T1_DQS_33_Y20") (pintype "passive"))
    )
    (net (code "219") (name "unconnected-(DD1C-IO_L12N_T1_MRCC_33-PadAA18)") (class "Default")
      (node (ref "DD1") (pin "AA18") (pinfunction "IO_L12N_T1_MRCC_33_AA18") (pintype "passive"))
    )
    (net (code "220") (name "unconnected-(DD1C-IO_L12P_T1_MRCC_33-PadY18)") (class "Default")
      (node (ref "DD1") (pin "Y18") (pinfunction "IO_L12P_T1_MRCC_33_Y18") (pintype "passive"))
    )
    (net (code "221") (name "unconnected-(DD1C-IO_L13N_T2_MRCC_33-PadW18)") (class "Default")
      (node (ref "DD1") (pin "W18") (pinfunction "IO_L13N_T2_MRCC_33_W18") (pintype "passive"))
    )
    (net (code "222") (name "unconnected-(DD1C-IO_L13P_T2_MRCC_33-PadW17)") (class "Default")
      (node (ref "DD1") (pin "W17") (pinfunction "IO_L13P_T2_MRCC_33_W17") (pintype "passive"))
    )
    (net (code "223") (name "unconnected-(DD1C-IO_L19N_T3_VREF_33-PadV15)") (class "Default")
      (node (ref "DD1") (pin "V15") (pinfunction "IO_L19N_T3_VREF_33_V15") (pintype "passive"))
    )
    (net (code "224") (name "unconnected-(DD1C-IO_L21N_T3_DQS_33-PadY15)") (class "Default")
      (node (ref "DD1") (pin "Y15") (pinfunction "IO_L21N_T3_DQS_33_Y15") (pintype "passive"))
    )
    (net (code "225") (name "unconnected-(DD1C-IO_L21P_T3_DQS_33-PadW15)") (class "Default")
      (node (ref "DD1") (pin "W15") (pinfunction "IO_L21P_T3_DQS_33_W15") (pintype "passive"))
    )
    (net (code "226") (name "unconnected-(DD1D-IO_0_34-PadH15)") (class "Default")
      (node (ref "DD1") (pin "H15") (pinfunction "IO_0_34_H15") (pintype "passive"))
    )
    (net (code "227") (name "unconnected-(DD1D-IO_25_34-PadR15)") (class "Default")
      (node (ref "DD1") (pin "R15") (pinfunction "IO_25_34_R15") (pintype "passive"))
    )
    (net (code "228") (name "unconnected-(DD1D-IO_L3N_T0_DQS_34-PadL16)") (class "Default")
      (node (ref "DD1") (pin "L16") (pinfunction "IO_L3N_T0_DQS_34_L16") (pintype "passive"))
    )
    (net (code "229") (name "unconnected-(DD1D-IO_L14N_T2_SRCC_34-PadN20)") (class "Default")
      (node (ref "DD1") (pin "N20") (pinfunction "IO_L14N_T2_SRCC_34_N20") (pintype "passive"))
    )
    (net (code "230") (name "unconnected-(DD1D-IO_L14P_T2_SRCC_34-PadN19)") (class "Default")
      (node (ref "DD1") (pin "N19") (pinfunction "IO_L14P_T2_SRCC_34_N19") (pintype "passive"))
    )
    (net (code "231") (name "unconnected-(DD1D-IO_L19N_T3_VREF_34-PadP15)") (class "Default")
      (node (ref "DD1") (pin "P15") (pinfunction "IO_L19N_T3_VREF_34_P15") (pintype "passive"))
    )
    (net (code "232") (name "unconnected-(DD1D-IO_L19P_T3_34-PadN15)") (class "Default")
      (node (ref "DD1") (pin "N15") (pinfunction "IO_L19P_T3_34_N15") (pintype "passive"))
    )
    (net (code "233") (name "unconnected-(DD1D-IO_L21N_T3_DQS_34-PadT17)") (class "Default")
      (node (ref "DD1") (pin "T17") (pinfunction "IO_L21N_T3_DQS_34_T17") (pintype "passive"))
    )
    (net (code "234") (name "unconnected-(DD1D-IO_L22N_T3_34-PadT19)") (class "Default")
      (node (ref "DD1") (pin "T19") (pinfunction "IO_L22N_T3_34_T19") (pintype "passive"))
    )
    (net (code "235") (name "unconnected-(DD1D-IO_L22P_T3_34-PadR19)") (class "Default")
      (node (ref "DD1") (pin "R19") (pinfunction "IO_L22P_T3_34_R19") (pintype "passive"))
    )
    (net (code "236") (name "unconnected-(DD1D-IO_L24N_T3_34-PadR16)") (class "Default")
      (node (ref "DD1") (pin "R16") (pinfunction "IO_L24N_T3_34_R16") (pintype "passive"))
    )
    (net (code "237") (name "unconnected-(DD1D-IO_L24P_T3_34-PadP16)") (class "Default")
      (node (ref "DD1") (pin "P16") (pinfunction "IO_L24P_T3_34_P16") (pintype "passive"))
    )
    (net (code "238") (name "unconnected-(DD1E-IO_25_35-PadH18)") (class "Default")
      (node (ref "DD1") (pin "H18") (pinfunction "IO_25_35_H18") (pintype "passive"))
    )
    (net (code "239") (name "unconnected-(DD1E-IO_L1N_T0_AD0N_35-PadE16)") (class "Default")
      (node (ref "DD1") (pin "E16") (pinfunction "IO_L1N_T0_AD0N_35_E16") (pintype "passive"))
    )
    (net (code "240") (name "unconnected-(DD1E-IO_L1P_T0_AD0P_35-PadF16)") (class "Default")
      (node (ref "DD1") (pin "F16") (pinfunction "IO_L1P_T0_AD0P_35_F16") (pintype "passive"))
    )
    (net (code "241") (name "unconnected-(DD1E-IO_L3N_T0_DQS_AD1N_35-PadD15)") (class "Default")
      (node (ref "DD1") (pin "D15") (pinfunction "IO_L3N_T0_DQS_AD1N_35_D15") (pintype "passive"))
    )
    (net (code "242") (name "unconnected-(DD1E-IO_L3P_T0_DQS_AD1P_35-PadE15)") (class "Default")
      (node (ref "DD1") (pin "E15") (pinfunction "IO_L3P_T0_DQS_AD1P_35_E15") (pintype "passive"))
    )
    (net (code "243") (name "unconnected-(DD1E-IO_L4N_T0_35-PadG16)") (class "Default")
      (node (ref "DD1") (pin "G16") (pinfunction "IO_L4N_T0_35_G16") (pintype "passive"))
    )
    (net (code "244") (name "unconnected-(DD1E-IO_L4P_T0_35-PadG15)") (class "Default")
      (node (ref "DD1") (pin "G15") (pinfunction "IO_L4P_T0_35_G15") (pintype "passive"))
    )
    (net (code "245") (name "unconnected-(DD1E-IO_L6N_T0_VREF_35-PadF17)") (class "Default")
      (node (ref "DD1") (pin "F17") (pinfunction "IO_L6N_T0_VREF_35_F17") (pintype "passive"))
    )
    (net (code "246") (name "unconnected-(DD1E-IO_L6P_T0_35-PadG17)") (class "Default")
      (node (ref "DD1") (pin "G17") (pinfunction "IO_L6P_T0_35_G17") (pintype "passive"))
    )
    (net (code "247") (name "unconnected-(DD1E-IO_L19N_T3_VREF_35-PadH20)") (class "Default")
      (node (ref "DD1") (pin "H20") (pinfunction "IO_L19N_T3_VREF_35_H20") (pintype "passive"))
    )
    (net (code "248") (name "unconnected-(DD1E-IO_L19P_T3_35-PadH19)") (class "Default")
      (node (ref "DD1") (pin "H19") (pinfunction "IO_L19P_T3_35_H19") (pintype "passive"))
    )
    (net (code "249") (name "unconnected-(DD1E-IO_L20N_T3_AD6N_35-PadF19)") (class "Default")
      (node (ref "DD1") (pin "F19") (pinfunction "IO_L20N_T3_AD6N_35_F19") (pintype "passive"))
    )
    (net (code "250") (name "unconnected-(DD1E-IO_L20P_T3_AD6P_35-PadG19)") (class "Default")
      (node (ref "DD1") (pin "G19") (pinfunction "IO_L20P_T3_AD6P_35_G19") (pintype "passive"))
    )
    (net (code "251") (name "unconnected-(DD1E-IO_L22N_T3_AD7N_35-PadG21)") (class "Default")
      (node (ref "DD1") (pin "G21") (pinfunction "IO_L22N_T3_AD7N_35_G21") (pintype "passive"))
    )
    (net (code "252") (name "unconnected-(DD1E-IO_L22P_T3_AD7P_35-PadG20)") (class "Default")
      (node (ref "DD1") (pin "G20") (pinfunction "IO_L22P_T3_AD7P_35_G20") (pintype "passive"))
    )
    (net (code "253") (name "unconnected-(DD7A-LDO_O-Pad43)") (class "Default")
      (node (ref "DD7") (pin "43") (pinfunction "LDO_O_43") (pintype "output"))
    )
    (net (code "254") (name "unconnected-(DD7B-NC-Pad13)") (class "Default")
      (node (ref "DD7") (pin "13") (pinfunction "NC_13") (pintype "passive"))
    )
    (net (code "255") (name "unconnected-(DD7B-NC-Pad47)") (class "Default")
      (node (ref "DD7") (pin "47") (pinfunction "NC_47") (pintype "passive"))
    )
  )
)
